# LEDpanel7-20.net
KiCad netlist of a schematic drawn in EAGLE
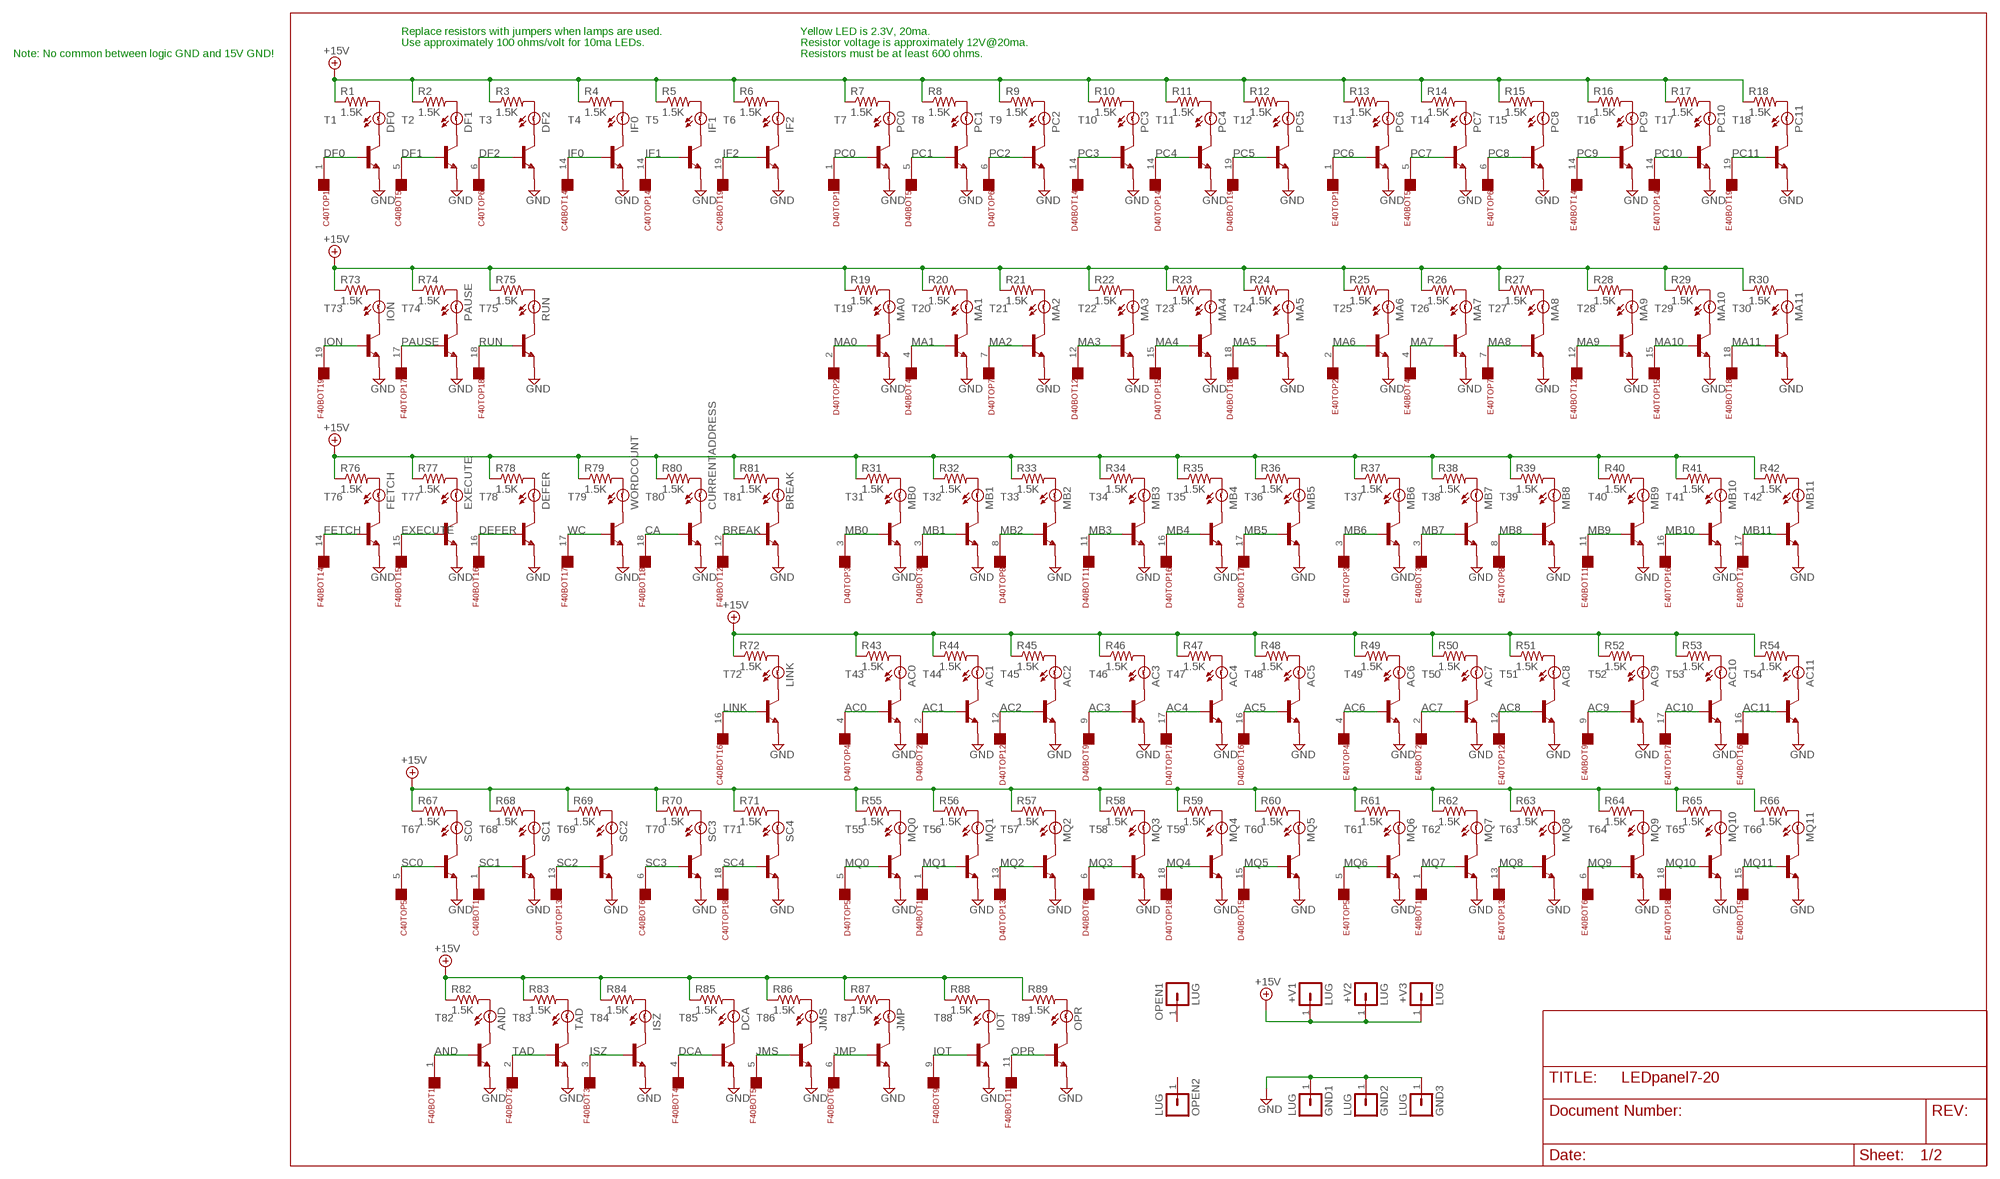
[diagram p0: schematic, sheet 1]
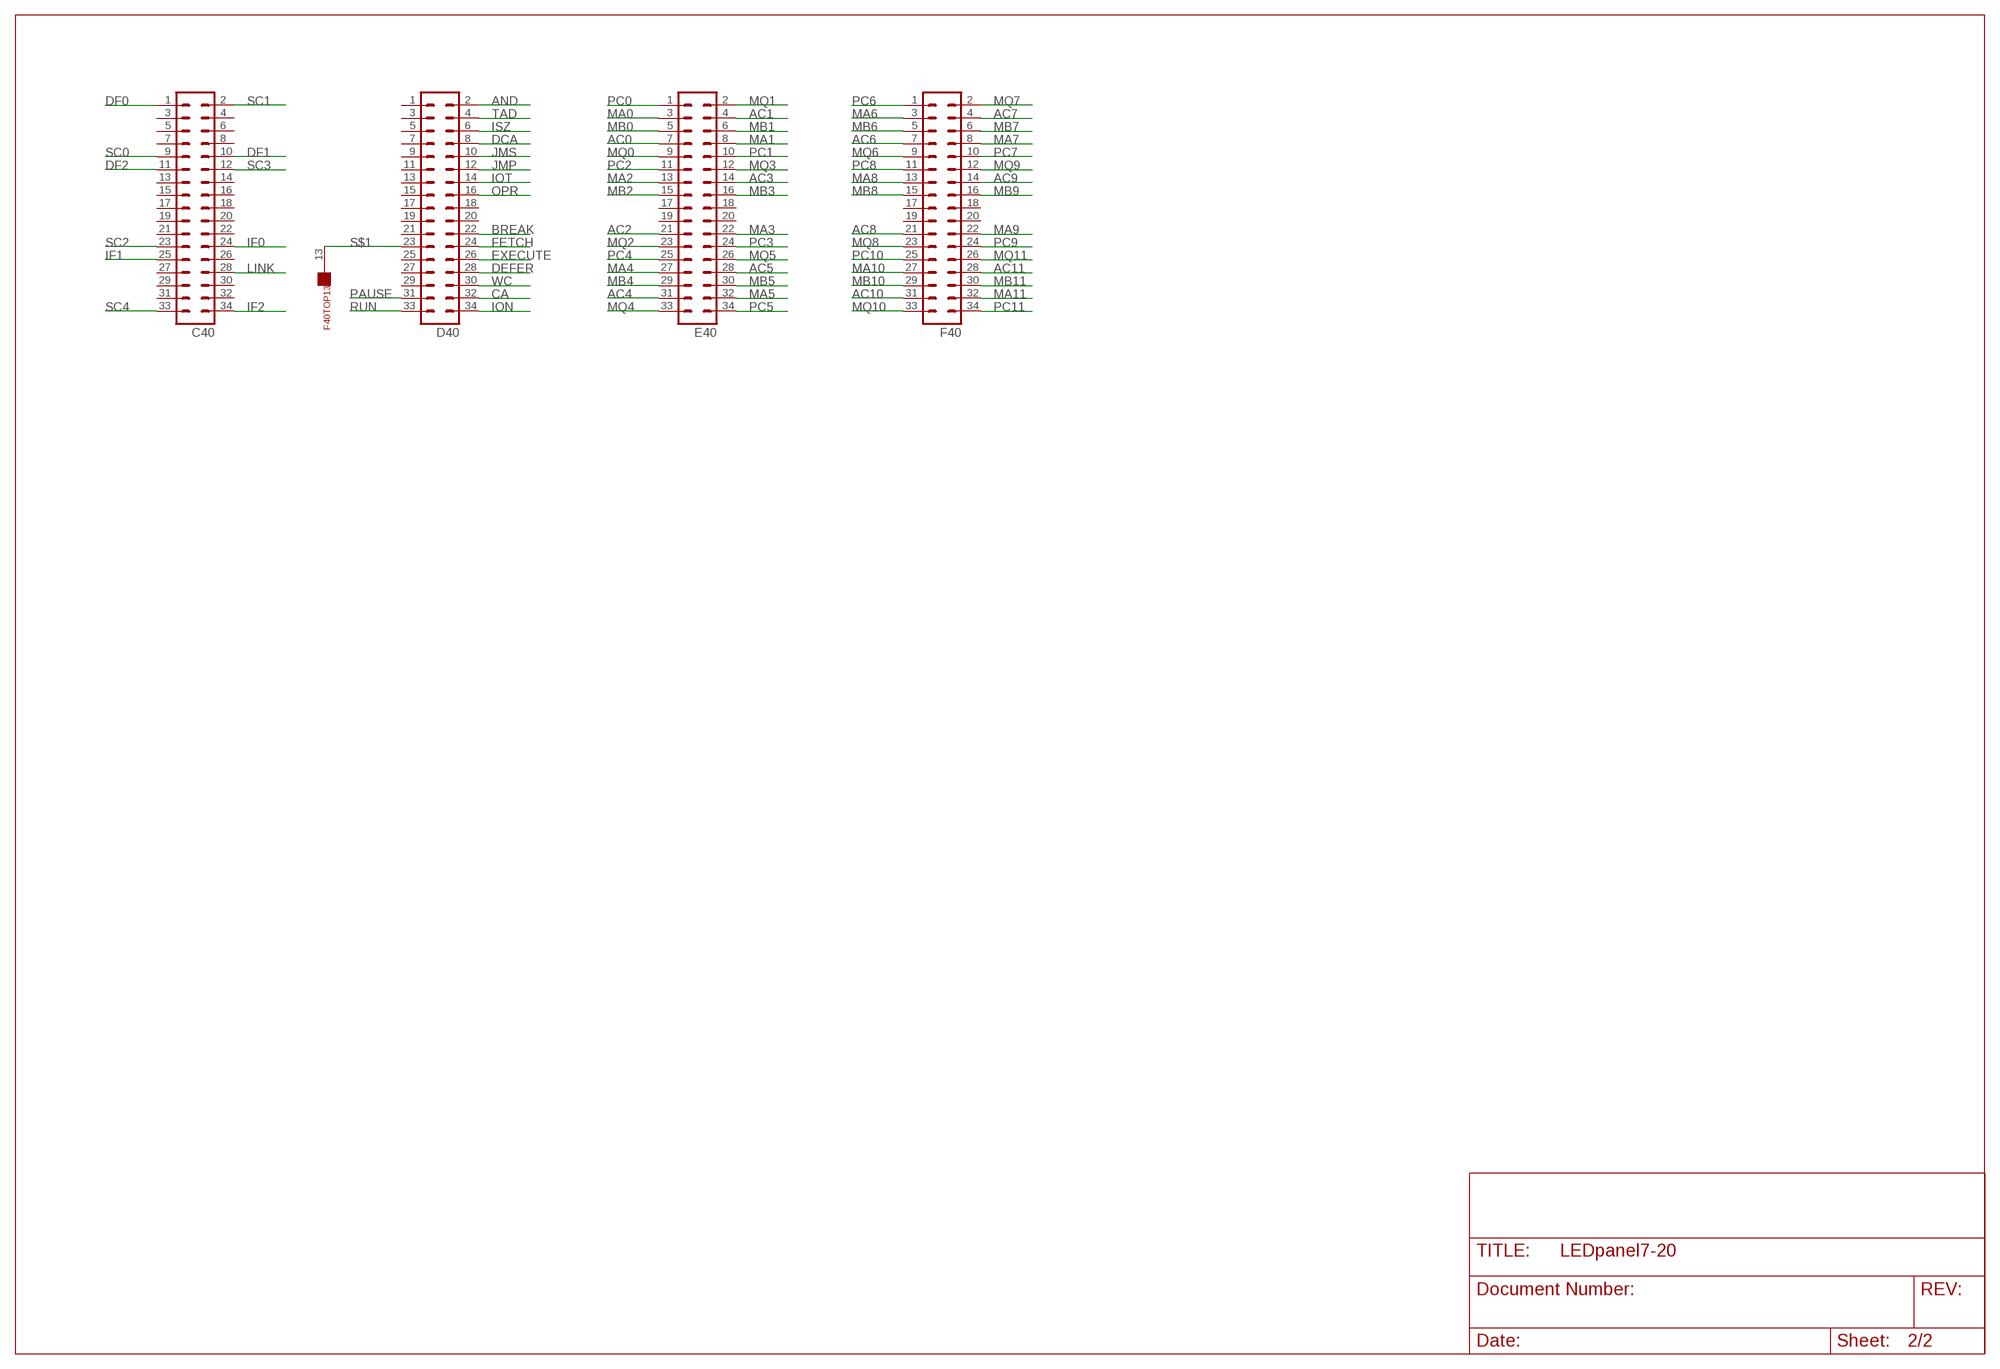
[diagram p1: schematic, sheet 2]

(export (version "E")
  (design (tool "Eeschema 10.0.6"))
  (components
    (comp (ref "C40")
      (value "ML34")
      (footprint "eagle-import:ML34")
      (libsource (lib "eagle-import") (part "ML34"))
    )
    (comp (ref "D40")
      (value "ML34")
      (footprint "eagle-import:ML34")
      (libsource (lib "eagle-import") (part "ML34"))
    )
    (comp (ref "E40")
      (value "ML34")
      (footprint "eagle-import:ML34")
      (libsource (lib "eagle-import") (part "ML34"))
    )
    (comp (ref "F40")
      (value "ML34")
      (footprint "eagle-import:ML34")
      (libsource (lib "eagle-import") (part "ML34"))
    )
    (comp (ref "F40TOP")
      (value "FLEX19")
      (footprint "eagle-import:FLEX19")
      (libsource (lib "eagle-import") (part "FLEX19"))
    )
    (comp (ref "+V1")
      (value "LUG")
      (footprint "eagle-import:SPADELUG")
      (libsource (lib "eagle-import") (part "LUG"))
    )
    (comp (ref "+V2")
      (value "LUG")
      (footprint "eagle-import:SPADELUG")
      (libsource (lib "eagle-import") (part "LUG"))
    )
    (comp (ref "+V3")
      (value "LUG")
      (footprint "eagle-import:SPADELUG")
      (libsource (lib "eagle-import") (part "LUG"))
    )
    (comp (ref "AC0")
      (value "BULB")
      (footprint "eagle-import:BULB")
      (libsource (lib "eagle-import") (part "BULB"))
    )
    (comp (ref "AC1")
      (value "BULB")
      (footprint "eagle-import:BULB")
      (libsource (lib "eagle-import") (part "BULB"))
    )
    (comp (ref "AC2")
      (value "BULB")
      (footprint "eagle-import:BULB")
      (libsource (lib "eagle-import") (part "BULB"))
    )
    (comp (ref "AC3")
      (value "BULB")
      (footprint "eagle-import:BULB")
      (libsource (lib "eagle-import") (part "BULB"))
    )
    (comp (ref "AC4")
      (value "BULB")
      (footprint "eagle-import:BULB")
      (libsource (lib "eagle-import") (part "BULB"))
    )
    (comp (ref "AC5")
      (value "BULB")
      (footprint "eagle-import:BULB")
      (libsource (lib "eagle-import") (part "BULB"))
    )
    (comp (ref "AC6")
      (value "BULB")
      (footprint "eagle-import:BULB")
      (libsource (lib "eagle-import") (part "BULB"))
    )
    (comp (ref "AC7")
      (value "BULB")
      (footprint "eagle-import:BULB")
      (libsource (lib "eagle-import") (part "BULB"))
    )
    (comp (ref "AC8")
      (value "BULB")
      (footprint "eagle-import:BULB")
      (libsource (lib "eagle-import") (part "BULB"))
    )
    (comp (ref "AC9")
      (value "BULB")
      (footprint "eagle-import:BULB")
      (libsource (lib "eagle-import") (part "BULB"))
    )
    (comp (ref "AC10")
      (value "BULB")
      (footprint "eagle-import:BULB")
      (libsource (lib "eagle-import") (part "BULB"))
    )
    (comp (ref "AC11")
      (value "BULB")
      (footprint "eagle-import:BULB")
      (libsource (lib "eagle-import") (part "BULB"))
    )
    (comp (ref "AND")
      (value "BULB")
      (footprint "eagle-import:BULB")
      (libsource (lib "eagle-import") (part "BULB"))
    )
    (comp (ref "BREAK")
      (value "BULB")
      (footprint "eagle-import:BULB")
      (libsource (lib "eagle-import") (part "BULB"))
    )
    (comp (ref "C40BOT")
      (value "FLEX19")
      (footprint "eagle-import:FLEX19")
      (libsource (lib "eagle-import") (part "FLEX19"))
    )
    (comp (ref "C40TOP")
      (value "FLEX19")
      (footprint "eagle-import:FLEX19")
      (libsource (lib "eagle-import") (part "FLEX19"))
    )
    (comp (ref "CURRENTADDRESS")
      (value "BULB")
      (footprint "eagle-import:BULB")
      (libsource (lib "eagle-import") (part "BULB"))
    )
    (comp (ref "D40BOT")
      (value "FLEX19")
      (footprint "eagle-import:FLEX19")
      (libsource (lib "eagle-import") (part "FLEX19"))
    )
    (comp (ref "D40TOP")
      (value "FLEX19")
      (footprint "eagle-import:FLEX19")
      (libsource (lib "eagle-import") (part "FLEX19"))
    )
    (comp (ref "DCA")
      (value "BULB")
      (footprint "eagle-import:BULB")
      (libsource (lib "eagle-import") (part "BULB"))
    )
    (comp (ref "DEFER")
      (value "BULB")
      (footprint "eagle-import:BULB")
      (libsource (lib "eagle-import") (part "BULB"))
    )
    (comp (ref "DF0")
      (value "BULB")
      (footprint "eagle-import:BULB")
      (libsource (lib "eagle-import") (part "BULB"))
    )
    (comp (ref "DF1")
      (value "BULB")
      (footprint "eagle-import:BULB")
      (libsource (lib "eagle-import") (part "BULB"))
    )
    (comp (ref "DF2")
      (value "BULB")
      (footprint "eagle-import:BULB")
      (libsource (lib "eagle-import") (part "BULB"))
    )
    (comp (ref "E40BOT")
      (value "FLEX19")
      (footprint "eagle-import:FLEX19")
      (libsource (lib "eagle-import") (part "FLEX19"))
    )
    (comp (ref "E40TOP")
      (value "FLEX19")
      (footprint "eagle-import:FLEX19")
      (libsource (lib "eagle-import") (part "FLEX19"))
    )
    (comp (ref "EXECUTE")
      (value "BULB")
      (footprint "eagle-import:BULB")
      (libsource (lib "eagle-import") (part "BULB"))
    )
    (comp (ref "F40BOT")
      (value "FLEX19")
      (footprint "eagle-import:FLEX19")
      (libsource (lib "eagle-import") (part "FLEX19"))
    )
    (comp (ref "FETCH")
      (value "BULB")
      (footprint "eagle-import:BULB")
      (libsource (lib "eagle-import") (part "BULB"))
    )
    (comp (ref "GND1")
      (value "LUG")
      (footprint "eagle-import:SPADELUG")
      (libsource (lib "eagle-import") (part "LUG"))
    )
    (comp (ref "GND2")
      (value "LUG")
      (footprint "eagle-import:SPADELUG")
      (libsource (lib "eagle-import") (part "LUG"))
    )
    (comp (ref "GND3")
      (value "LUG")
      (footprint "eagle-import:SPADELUG")
      (libsource (lib "eagle-import") (part "LUG"))
    )
    (comp (ref "IF0")
      (value "BULB")
      (footprint "eagle-import:BULB")
      (libsource (lib "eagle-import") (part "BULB"))
    )
    (comp (ref "IF1")
      (value "BULB")
      (footprint "eagle-import:BULB")
      (libsource (lib "eagle-import") (part "BULB"))
    )
    (comp (ref "IF2")
      (value "BULB")
      (footprint "eagle-import:BULB")
      (libsource (lib "eagle-import") (part "BULB"))
    )
    (comp (ref "ION")
      (value "BULB")
      (footprint "eagle-import:BULB")
      (libsource (lib "eagle-import") (part "BULB"))
    )
    (comp (ref "IOT")
      (value "BULB")
      (footprint "eagle-import:BULB")
      (libsource (lib "eagle-import") (part "BULB"))
    )
    (comp (ref "ISZ")
      (value "BULB")
      (footprint "eagle-import:BULB")
      (libsource (lib "eagle-import") (part "BULB"))
    )
    (comp (ref "JMP")
      (value "BULB")
      (footprint "eagle-import:BULB")
      (libsource (lib "eagle-import") (part "BULB"))
    )
    (comp (ref "JMS")
      (value "BULB")
      (footprint "eagle-import:BULB")
      (libsource (lib "eagle-import") (part "BULB"))
    )
    (comp (ref "LINK")
      (value "BULB")
      (footprint "eagle-import:BULB")
      (libsource (lib "eagle-import") (part "BULB"))
    )
    (comp (ref "MA0")
      (value "BULB")
      (footprint "eagle-import:BULB")
      (libsource (lib "eagle-import") (part "BULB"))
    )
    (comp (ref "MA1")
      (value "BULB")
      (footprint "eagle-import:BULB")
      (libsource (lib "eagle-import") (part "BULB"))
    )
    (comp (ref "MA2")
      (value "BULB")
      (footprint "eagle-import:BULB")
      (libsource (lib "eagle-import") (part "BULB"))
    )
    (comp (ref "MA3")
      (value "BULB")
      (footprint "eagle-import:BULB")
      (libsource (lib "eagle-import") (part "BULB"))
    )
    (comp (ref "MA4")
      (value "BULB")
      (footprint "eagle-import:BULB")
      (libsource (lib "eagle-import") (part "BULB"))
    )
    (comp (ref "MA5")
      (value "BULB")
      (footprint "eagle-import:BULB")
      (libsource (lib "eagle-import") (part "BULB"))
    )
    (comp (ref "MA6")
      (value "BULB")
      (footprint "eagle-import:BULB")
      (libsource (lib "eagle-import") (part "BULB"))
    )
    (comp (ref "MA7")
      (value "BULB")
      (footprint "eagle-import:BULB")
      (libsource (lib "eagle-import") (part "BULB"))
    )
    (comp (ref "MA8")
      (value "BULB")
      (footprint "eagle-import:BULB")
      (libsource (lib "eagle-import") (part "BULB"))
    )
    (comp (ref "MA9")
      (value "BULB")
      (footprint "eagle-import:BULB")
      (libsource (lib "eagle-import") (part "BULB"))
    )
    (comp (ref "MA10")
      (value "BULB")
      (footprint "eagle-import:BULB")
      (libsource (lib "eagle-import") (part "BULB"))
    )
    (comp (ref "MA11")
      (value "BULB")
      (footprint "eagle-import:BULB")
      (libsource (lib "eagle-import") (part "BULB"))
    )
    (comp (ref "MB0")
      (value "BULB")
      (footprint "eagle-import:BULB")
      (libsource (lib "eagle-import") (part "BULB"))
    )
    (comp (ref "MB1")
      (value "BULB")
      (footprint "eagle-import:BULB")
      (libsource (lib "eagle-import") (part "BULB"))
    )
    (comp (ref "MB2")
      (value "BULB")
      (footprint "eagle-import:BULB")
      (libsource (lib "eagle-import") (part "BULB"))
    )
    (comp (ref "MB3")
      (value "BULB")
      (footprint "eagle-import:BULB")
      (libsource (lib "eagle-import") (part "BULB"))
    )
    (comp (ref "MB4")
      (value "BULB")
      (footprint "eagle-import:BULB")
      (libsource (lib "eagle-import") (part "BULB"))
    )
    (comp (ref "MB5")
      (value "BULB")
      (footprint "eagle-import:BULB")
      (libsource (lib "eagle-import") (part "BULB"))
    )
    (comp (ref "MB6")
      (value "BULB")
      (footprint "eagle-import:BULB")
      (libsource (lib "eagle-import") (part "BULB"))
    )
    (comp (ref "MB7")
      (value "BULB")
      (footprint "eagle-import:BULB")
      (libsource (lib "eagle-import") (part "BULB"))
    )
    (comp (ref "MB8")
      (value "BULB")
      (footprint "eagle-import:BULB")
      (libsource (lib "eagle-import") (part "BULB"))
    )
    (comp (ref "MB9")
      (value "BULB")
      (footprint "eagle-import:BULB")
      (libsource (lib "eagle-import") (part "BULB"))
    )
    (comp (ref "MB10")
      (value "BULB")
      (footprint "eagle-import:BULB")
      (libsource (lib "eagle-import") (part "BULB"))
    )
    (comp (ref "MB11")
      (value "BULB")
      (footprint "eagle-import:BULB")
      (libsource (lib "eagle-import") (part "BULB"))
    )
    (comp (ref "MQ0")
      (value "BULB")
      (footprint "eagle-import:BULB")
      (libsource (lib "eagle-import") (part "BULB"))
    )
    (comp (ref "MQ1")
      (value "BULB")
      (footprint "eagle-import:BULB")
      (libsource (lib "eagle-import") (part "BULB"))
    )
    (comp (ref "MQ2")
      (value "BULB")
      (footprint "eagle-import:BULB")
      (libsource (lib "eagle-import") (part "BULB"))
    )
    (comp (ref "MQ3")
      (value "BULB")
      (footprint "eagle-import:BULB")
      (libsource (lib "eagle-import") (part "BULB"))
    )
    (comp (ref "MQ4")
      (value "BULB")
      (footprint "eagle-import:BULB")
      (libsource (lib "eagle-import") (part "BULB"))
    )
    (comp (ref "MQ5")
      (value "BULB")
      (footprint "eagle-import:BULB")
      (libsource (lib "eagle-import") (part "BULB"))
    )
    (comp (ref "MQ6")
      (value "BULB")
      (footprint "eagle-import:BULB")
      (libsource (lib "eagle-import") (part "BULB"))
    )
    (comp (ref "MQ7")
      (value "BULB")
      (footprint "eagle-import:BULB")
      (libsource (lib "eagle-import") (part "BULB"))
    )
    (comp (ref "MQ8")
      (value "BULB")
      (footprint "eagle-import:BULB")
      (libsource (lib "eagle-import") (part "BULB"))
    )
    (comp (ref "MQ9")
      (value "BULB")
      (footprint "eagle-import:BULB")
      (libsource (lib "eagle-import") (part "BULB"))
    )
    (comp (ref "MQ10")
      (value "BULB")
      (footprint "eagle-import:BULB")
      (libsource (lib "eagle-import") (part "BULB"))
    )
    (comp (ref "MQ11")
      (value "BULB")
      (footprint "eagle-import:BULB")
      (libsource (lib "eagle-import") (part "BULB"))
    )
    (comp (ref "OPEN1")
      (value "LUG")
      (footprint "eagle-import:SPADELUG")
      (libsource (lib "eagle-import") (part "LUG"))
    )
    (comp (ref "OPEN2")
      (value "LUG")
      (footprint "eagle-import:SPADELUG")
      (libsource (lib "eagle-import") (part "LUG"))
    )
    (comp (ref "OPR")
      (value "BULB")
      (footprint "eagle-import:BULB")
      (libsource (lib "eagle-import") (part "BULB"))
    )
    (comp (ref "PAUSE")
      (value "BULB")
      (footprint "eagle-import:BULB")
      (libsource (lib "eagle-import") (part "BULB"))
    )
    (comp (ref "PC0")
      (value "BULB")
      (footprint "eagle-import:BULB")
      (libsource (lib "eagle-import") (part "BULB"))
    )
    (comp (ref "PC1")
      (value "BULB")
      (footprint "eagle-import:BULB")
      (libsource (lib "eagle-import") (part "BULB"))
    )
    (comp (ref "PC2")
      (value "BULB")
      (footprint "eagle-import:BULB")
      (libsource (lib "eagle-import") (part "BULB"))
    )
    (comp (ref "PC3")
      (value "BULB")
      (footprint "eagle-import:BULB")
      (libsource (lib "eagle-import") (part "BULB"))
    )
    (comp (ref "PC4")
      (value "BULB")
      (footprint "eagle-import:BULB")
      (libsource (lib "eagle-import") (part "BULB"))
    )
    (comp (ref "PC5")
      (value "BULB")
      (footprint "eagle-import:BULB")
      (libsource (lib "eagle-import") (part "BULB"))
    )
    (comp (ref "PC6")
      (value "BULB")
      (footprint "eagle-import:BULB")
      (libsource (lib "eagle-import") (part "BULB"))
    )
    (comp (ref "PC7")
      (value "BULB")
      (footprint "eagle-import:BULB")
      (libsource (lib "eagle-import") (part "BULB"))
    )
    (comp (ref "PC8")
      (value "BULB")
      (footprint "eagle-import:BULB")
      (libsource (lib "eagle-import") (part "BULB"))
    )
    (comp (ref "PC9")
      (value "BULB")
      (footprint "eagle-import:BULB")
      (libsource (lib "eagle-import") (part "BULB"))
    )
    (comp (ref "PC10")
      (value "BULB")
      (footprint "eagle-import:BULB")
      (libsource (lib "eagle-import") (part "BULB"))
    )
    (comp (ref "PC11")
      (value "BULB")
      (footprint "eagle-import:BULB")
      (libsource (lib "eagle-import") (part "BULB"))
    )
    (comp (ref "R1")
      (value "1.5K")
      (footprint "eagle-import:0207_10")
      (libsource (lib "eagle-import") (part "R-US_0207/10"))
    )
    (comp (ref "R2")
      (value "1.5K")
      (footprint "eagle-import:0207_10")
      (libsource (lib "eagle-import") (part "R-US_0207/10"))
    )
    (comp (ref "R3")
      (value "1.5K")
      (footprint "eagle-import:0207_10")
      (libsource (lib "eagle-import") (part "R-US_0207/10"))
    )
    (comp (ref "R4")
      (value "1.5K")
      (footprint "eagle-import:0207_10")
      (libsource (lib "eagle-import") (part "R-US_0207/10"))
    )
    (comp (ref "R5")
      (value "1.5K")
      (footprint "eagle-import:0207_10")
      (libsource (lib "eagle-import") (part "R-US_0207/10"))
    )
    (comp (ref "R6")
      (value "1.5K")
      (footprint "eagle-import:0207_10")
      (libsource (lib "eagle-import") (part "R-US_0207/10"))
    )
    (comp (ref "R7")
      (value "1.5K")
      (footprint "eagle-import:0207_10")
      (libsource (lib "eagle-import") (part "R-US_0207/10"))
    )
    (comp (ref "R8")
      (value "1.5K")
      (footprint "eagle-import:0207_10")
      (libsource (lib "eagle-import") (part "R-US_0207/10"))
    )
    (comp (ref "R9")
      (value "1.5K")
      (footprint "eagle-import:0207_10")
      (libsource (lib "eagle-import") (part "R-US_0207/10"))
    )
    (comp (ref "R10")
      (value "1.5K")
      (footprint "eagle-import:0207_10")
      (libsource (lib "eagle-import") (part "R-US_0207/10"))
    )
    (comp (ref "R11")
      (value "1.5K")
      (footprint "eagle-import:0207_10")
      (libsource (lib "eagle-import") (part "R-US_0207/10"))
    )
    (comp (ref "R12")
      (value "1.5K")
      (footprint "eagle-import:0207_10")
      (libsource (lib "eagle-import") (part "R-US_0207/10"))
    )
    (comp (ref "R13")
      (value "1.5K")
      (footprint "eagle-import:0207_10")
      (libsource (lib "eagle-import") (part "R-US_0207/10"))
    )
    (comp (ref "R14")
      (value "1.5K")
      (footprint "eagle-import:0207_10")
      (libsource (lib "eagle-import") (part "R-US_0207/10"))
    )
    (comp (ref "R15")
      (value "1.5K")
      (footprint "eagle-import:0207_10")
      (libsource (lib "eagle-import") (part "R-US_0207/10"))
    )
    (comp (ref "R16")
      (value "1.5K")
      (footprint "eagle-import:0207_10")
      (libsource (lib "eagle-import") (part "R-US_0207/10"))
    )
    (comp (ref "R17")
      (value "1.5K")
      (footprint "eagle-import:0207_10")
      (libsource (lib "eagle-import") (part "R-US_0207/10"))
    )
    (comp (ref "R18")
      (value "1.5K")
      (footprint "eagle-import:0207_10")
      (libsource (lib "eagle-import") (part "R-US_0207/10"))
    )
    (comp (ref "R19")
      (value "1.5K")
      (footprint "eagle-import:0207_10")
      (libsource (lib "eagle-import") (part "R-US_0207/10"))
    )
    (comp (ref "R20")
      (value "1.5K")
      (footprint "eagle-import:0207_10")
      (libsource (lib "eagle-import") (part "R-US_0207/10"))
    )
    (comp (ref "R21")
      (value "1.5K")
      (footprint "eagle-import:0207_10")
      (libsource (lib "eagle-import") (part "R-US_0207/10"))
    )
    (comp (ref "R22")
      (value "1.5K")
      (footprint "eagle-import:0207_10")
      (libsource (lib "eagle-import") (part "R-US_0207/10"))
    )
    (comp (ref "R23")
      (value "1.5K")
      (footprint "eagle-import:0207_10")
      (libsource (lib "eagle-import") (part "R-US_0207/10"))
    )
    (comp (ref "R24")
      (value "1.5K")
      (footprint "eagle-import:0207_10")
      (libsource (lib "eagle-import") (part "R-US_0207/10"))
    )
    (comp (ref "R25")
      (value "1.5K")
      (footprint "eagle-import:0207_10")
      (libsource (lib "eagle-import") (part "R-US_0207/10"))
    )
    (comp (ref "R26")
      (value "1.5K")
      (footprint "eagle-import:0207_10")
      (libsource (lib "eagle-import") (part "R-US_0207/10"))
    )
    (comp (ref "R27")
      (value "1.5K")
      (footprint "eagle-import:0207_10")
      (libsource (lib "eagle-import") (part "R-US_0207/10"))
    )
    (comp (ref "R28")
      (value "1.5K")
      (footprint "eagle-import:0207_10")
      (libsource (lib "eagle-import") (part "R-US_0207/10"))
    )
    (comp (ref "R29")
      (value "1.5K")
      (footprint "eagle-import:0207_10")
      (libsource (lib "eagle-import") (part "R-US_0207/10"))
    )
    (comp (ref "R30")
      (value "1.5K")
      (footprint "eagle-import:0207_10")
      (libsource (lib "eagle-import") (part "R-US_0207/10"))
    )
    (comp (ref "R31")
      (value "1.5K")
      (footprint "eagle-import:0207_10")
      (libsource (lib "eagle-import") (part "R-US_0207/10"))
    )
    (comp (ref "R32")
      (value "1.5K")
      (footprint "eagle-import:0207_10")
      (libsource (lib "eagle-import") (part "R-US_0207/10"))
    )
    (comp (ref "R33")
      (value "1.5K")
      (footprint "eagle-import:0207_10")
      (libsource (lib "eagle-import") (part "R-US_0207/10"))
    )
    (comp (ref "R34")
      (value "1.5K")
      (footprint "eagle-import:0207_10")
      (libsource (lib "eagle-import") (part "R-US_0207/10"))
    )
    (comp (ref "R35")
      (value "1.5K")
      (footprint "eagle-import:0207_10")
      (libsource (lib "eagle-import") (part "R-US_0207/10"))
    )
    (comp (ref "R36")
      (value "1.5K")
      (footprint "eagle-import:0207_10")
      (libsource (lib "eagle-import") (part "R-US_0207/10"))
    )
    (comp (ref "R37")
      (value "1.5K")
      (footprint "eagle-import:0207_10")
      (libsource (lib "eagle-import") (part "R-US_0207/10"))
    )
    (comp (ref "R38")
      (value "1.5K")
      (footprint "eagle-import:0207_10")
      (libsource (lib "eagle-import") (part "R-US_0207/10"))
    )
    (comp (ref "R39")
      (value "1.5K")
      (footprint "eagle-import:0207_10")
      (libsource (lib "eagle-import") (part "R-US_0207/10"))
    )
    (comp (ref "R40")
      (value "1.5K")
      (footprint "eagle-import:0207_10")
      (libsource (lib "eagle-import") (part "R-US_0207/10"))
    )
    (comp (ref "R41")
      (value "1.5K")
      (footprint "eagle-import:0207_10")
      (libsource (lib "eagle-import") (part "R-US_0207/10"))
    )
    (comp (ref "R42")
      (value "1.5K")
      (footprint "eagle-import:0207_10")
      (libsource (lib "eagle-import") (part "R-US_0207/10"))
    )
    (comp (ref "R43")
      (value "1.5K")
      (footprint "eagle-import:0207_10")
      (libsource (lib "eagle-import") (part "R-US_0207/10"))
    )
    (comp (ref "R44")
      (value "1.5K")
      (footprint "eagle-import:0207_10")
      (libsource (lib "eagle-import") (part "R-US_0207/10"))
    )
    (comp (ref "R45")
      (value "1.5K")
      (footprint "eagle-import:0207_10")
      (libsource (lib "eagle-import") (part "R-US_0207/10"))
    )
    (comp (ref "R46")
      (value "1.5K")
      (footprint "eagle-import:0207_10")
      (libsource (lib "eagle-import") (part "R-US_0207/10"))
    )
    (comp (ref "R47")
      (value "1.5K")
      (footprint "eagle-import:0207_10")
      (libsource (lib "eagle-import") (part "R-US_0207/10"))
    )
    (comp (ref "R48")
      (value "1.5K")
      (footprint "eagle-import:0207_10")
      (libsource (lib "eagle-import") (part "R-US_0207/10"))
    )
    (comp (ref "R49")
      (value "1.5K")
      (footprint "eagle-import:0207_10")
      (libsource (lib "eagle-import") (part "R-US_0207/10"))
    )
    (comp (ref "R50")
      (value "1.5K")
      (footprint "eagle-import:0207_10")
      (libsource (lib "eagle-import") (part "R-US_0207/10"))
    )
    (comp (ref "R51")
      (value "1.5K")
      (footprint "eagle-import:0207_10")
      (libsource (lib "eagle-import") (part "R-US_0207/10"))
    )
    (comp (ref "R52")
      (value "1.5K")
      (footprint "eagle-import:0207_10")
      (libsource (lib "eagle-import") (part "R-US_0207/10"))
    )
    (comp (ref "R53")
      (value "1.5K")
      (footprint "eagle-import:0207_10")
      (libsource (lib "eagle-import") (part "R-US_0207/10"))
    )
    (comp (ref "R54")
      (value "1.5K")
      (footprint "eagle-import:0207_10")
      (libsource (lib "eagle-import") (part "R-US_0207/10"))
    )
    (comp (ref "R55")
      (value "1.5K")
      (footprint "eagle-import:0207_10")
      (libsource (lib "eagle-import") (part "R-US_0207/10"))
    )
    (comp (ref "R56")
      (value "1.5K")
      (footprint "eagle-import:0207_10")
      (libsource (lib "eagle-import") (part "R-US_0207/10"))
    )
    (comp (ref "R57")
      (value "1.5K")
      (footprint "eagle-import:0207_10")
      (libsource (lib "eagle-import") (part "R-US_0207/10"))
    )
    (comp (ref "R58")
      (value "1.5K")
      (footprint "eagle-import:0207_10")
      (libsource (lib "eagle-import") (part "R-US_0207/10"))
    )
    (comp (ref "R59")
      (value "1.5K")
      (footprint "eagle-import:0207_10")
      (libsource (lib "eagle-import") (part "R-US_0207/10"))
    )
    (comp (ref "R60")
      (value "1.5K")
      (footprint "eagle-import:0207_10")
      (libsource (lib "eagle-import") (part "R-US_0207/10"))
    )
    (comp (ref "R61")
      (value "1.5K")
      (footprint "eagle-import:0207_10")
      (libsource (lib "eagle-import") (part "R-US_0207/10"))
    )
    (comp (ref "R62")
      (value "1.5K")
      (footprint "eagle-import:0207_10")
      (libsource (lib "eagle-import") (part "R-US_0207/10"))
    )
    (comp (ref "R63")
      (value "1.5K")
      (footprint "eagle-import:0207_10")
      (libsource (lib "eagle-import") (part "R-US_0207/10"))
    )
    (comp (ref "R64")
      (value "1.5K")
      (footprint "eagle-import:0207_10")
      (libsource (lib "eagle-import") (part "R-US_0207/10"))
    )
    (comp (ref "R65")
      (value "1.5K")
      (footprint "eagle-import:0207_10")
      (libsource (lib "eagle-import") (part "R-US_0207/10"))
    )
    (comp (ref "R66")
      (value "1.5K")
      (footprint "eagle-import:0207_10")
      (libsource (lib "eagle-import") (part "R-US_0207/10"))
    )
    (comp (ref "R67")
      (value "1.5K")
      (footprint "eagle-import:0207_10")
      (libsource (lib "eagle-import") (part "R-US_0207/10"))
    )
    (comp (ref "R68")
      (value "1.5K")
      (footprint "eagle-import:0207_10")
      (libsource (lib "eagle-import") (part "R-US_0207/10"))
    )
    (comp (ref "R69")
      (value "1.5K")
      (footprint "eagle-import:0207_10")
      (libsource (lib "eagle-import") (part "R-US_0207/10"))
    )
    (comp (ref "R70")
      (value "1.5K")
      (footprint "eagle-import:0207_10")
      (libsource (lib "eagle-import") (part "R-US_0207/10"))
    )
    (comp (ref "R71")
      (value "1.5K")
      (footprint "eagle-import:0207_10")
      (libsource (lib "eagle-import") (part "R-US_0207/10"))
    )
    (comp (ref "R72")
      (value "1.5K")
      (footprint "eagle-import:0207_10")
      (libsource (lib "eagle-import") (part "R-US_0207/10"))
    )
    (comp (ref "R73")
      (value "1.5K")
      (footprint "eagle-import:0207_10")
      (libsource (lib "eagle-import") (part "R-US_0207/10"))
    )
    (comp (ref "R74")
      (value "1.5K")
      (footprint "eagle-import:0207_10")
      (libsource (lib "eagle-import") (part "R-US_0207/10"))
    )
    (comp (ref "R75")
      (value "1.5K")
      (footprint "eagle-import:0207_10")
      (libsource (lib "eagle-import") (part "R-US_0207/10"))
    )
    (comp (ref "R76")
      (value "1.5K")
      (footprint "eagle-import:0207_10")
      (libsource (lib "eagle-import") (part "R-US_0207/10"))
    )
    (comp (ref "R77")
      (value "1.5K")
      (footprint "eagle-import:0207_10")
      (libsource (lib "eagle-import") (part "R-US_0207/10"))
    )
    (comp (ref "R78")
      (value "1.5K")
      (footprint "eagle-import:0207_10")
      (libsource (lib "eagle-import") (part "R-US_0207/10"))
    )
    (comp (ref "R79")
      (value "1.5K")
      (footprint "eagle-import:0207_10")
      (libsource (lib "eagle-import") (part "R-US_0207/10"))
    )
    (comp (ref "R80")
      (value "1.5K")
      (footprint "eagle-import:0207_10")
      (libsource (lib "eagle-import") (part "R-US_0207/10"))
    )
    (comp (ref "R81")
      (value "1.5K")
      (footprint "eagle-import:0207_10")
      (libsource (lib "eagle-import") (part "R-US_0207/10"))
    )
    (comp (ref "R82")
      (value "1.5K")
      (footprint "eagle-import:0207_10")
      (libsource (lib "eagle-import") (part "R-US_0207/10"))
    )
    (comp (ref "R83")
      (value "1.5K")
      (footprint "eagle-import:0207_10")
      (libsource (lib "eagle-import") (part "R-US_0207/10"))
    )
    (comp (ref "R84")
      (value "1.5K")
      (footprint "eagle-import:0207_10")
      (libsource (lib "eagle-import") (part "R-US_0207/10"))
    )
    (comp (ref "R85")
      (value "1.5K")
      (footprint "eagle-import:0207_10")
      (libsource (lib "eagle-import") (part "R-US_0207/10"))
    )
    (comp (ref "R86")
      (value "1.5K")
      (footprint "eagle-import:0207_10")
      (libsource (lib "eagle-import") (part "R-US_0207/10"))
    )
    (comp (ref "R87")
      (value "1.5K")
      (footprint "eagle-import:0207_10")
      (libsource (lib "eagle-import") (part "R-US_0207/10"))
    )
    (comp (ref "R88")
      (value "1.5K")
      (footprint "eagle-import:0207_10")
      (libsource (lib "eagle-import") (part "R-US_0207/10"))
    )
    (comp (ref "R89")
      (value "1.5K")
      (footprint "eagle-import:0207_10")
      (libsource (lib "eagle-import") (part "R-US_0207/10"))
    )
    (comp (ref "RUN")
      (value "BULB")
      (footprint "eagle-import:BULB")
      (libsource (lib "eagle-import") (part "BULB"))
    )
    (comp (ref "SC0")
      (value "BULB")
      (footprint "eagle-import:BULB")
      (libsource (lib "eagle-import") (part "BULB"))
    )
    (comp (ref "SC1")
      (value "BULB")
      (footprint "eagle-import:BULB")
      (libsource (lib "eagle-import") (part "BULB"))
    )
    (comp (ref "SC2")
      (value "BULB")
      (footprint "eagle-import:BULB")
      (libsource (lib "eagle-import") (part "BULB"))
    )
    (comp (ref "SC3")
      (value "BULB")
      (footprint "eagle-import:BULB")
      (libsource (lib "eagle-import") (part "BULB"))
    )
    (comp (ref "SC4")
      (value "BULB")
      (footprint "eagle-import:BULB")
      (libsource (lib "eagle-import") (part "BULB"))
    )
    (comp (ref "T1")
      (value "MPS2222A-NPN-TO92-CBE")
      (footprint "eagle-import:TO92-CBE")
      (libsource (lib "eagle-import") (part "-NPN-TO92-CBEMPS2222A"))
    )
    (comp (ref "T2")
      (value "MPS2222A-NPN-TO92-CBE")
      (footprint "eagle-import:TO92-CBE")
      (libsource (lib "eagle-import") (part "-NPN-TO92-CBEMPS2222A"))
    )
    (comp (ref "T3")
      (value "MPS2222A-NPN-TO92-CBE")
      (footprint "eagle-import:TO92-CBE")
      (libsource (lib "eagle-import") (part "-NPN-TO92-CBEMPS2222A"))
    )
    (comp (ref "T4")
      (value "MPS2222A-NPN-TO92-CBE")
      (footprint "eagle-import:TO92-CBE")
      (libsource (lib "eagle-import") (part "-NPN-TO92-CBEMPS2222A"))
    )
    (comp (ref "T5")
      (value "MPS2222A-NPN-TO92-CBE")
      (footprint "eagle-import:TO92-CBE")
      (libsource (lib "eagle-import") (part "-NPN-TO92-CBEMPS2222A"))
    )
    (comp (ref "T6")
      (value "MPS2222A-NPN-TO92-CBE")
      (footprint "eagle-import:TO92-CBE")
      (libsource (lib "eagle-import") (part "-NPN-TO92-CBEMPS2222A"))
    )
    (comp (ref "T7")
      (value "MPS2222A-NPN-TO92-CBE")
      (footprint "eagle-import:TO92-CBE")
      (libsource (lib "eagle-import") (part "-NPN-TO92-CBEMPS2222A"))
    )
    (comp (ref "T8")
      (value "MPS2222A-NPN-TO92-CBE")
      (footprint "eagle-import:TO92-CBE")
      (libsource (lib "eagle-import") (part "-NPN-TO92-CBEMPS2222A"))
    )
    (comp (ref "T9")
      (value "MPS2222A-NPN-TO92-CBE")
      (footprint "eagle-import:TO92-CBE")
      (libsource (lib "eagle-import") (part "-NPN-TO92-CBEMPS2222A"))
    )
    (comp (ref "T10")
      (value "MPS2222A-NPN-TO92-CBE")
      (footprint "eagle-import:TO92-CBE")
      (libsource (lib "eagle-import") (part "-NPN-TO92-CBEMPS2222A"))
    )
    (comp (ref "T11")
      (value "MPS2222A-NPN-TO92-CBE")
      (footprint "eagle-import:TO92-CBE")
      (libsource (lib "eagle-import") (part "-NPN-TO92-CBEMPS2222A"))
    )
    (comp (ref "T12")
      (value "MPS2222A-NPN-TO92-CBE")
      (footprint "eagle-import:TO92-CBE")
      (libsource (lib "eagle-import") (part "-NPN-TO92-CBEMPS2222A"))
    )
    (comp (ref "T13")
      (value "MPS2222A-NPN-TO92-CBE")
      (footprint "eagle-import:TO92-CBE")
      (libsource (lib "eagle-import") (part "-NPN-TO92-CBEMPS2222A"))
    )
    (comp (ref "T14")
      (value "MPS2222A-NPN-TO92-CBE")
      (footprint "eagle-import:TO92-CBE")
      (libsource (lib "eagle-import") (part "-NPN-TO92-CBEMPS2222A"))
    )
    (comp (ref "T15")
      (value "MPS2222A-NPN-TO92-CBE")
      (footprint "eagle-import:TO92-CBE")
      (libsource (lib "eagle-import") (part "-NPN-TO92-CBEMPS2222A"))
    )
    (comp (ref "T16")
      (value "MPS2222A-NPN-TO92-CBE")
      (footprint "eagle-import:TO92-CBE")
      (libsource (lib "eagle-import") (part "-NPN-TO92-CBEMPS2222A"))
    )
    (comp (ref "T17")
      (value "MPS2222A-NPN-TO92-CBE")
      (footprint "eagle-import:TO92-CBE")
      (libsource (lib "eagle-import") (part "-NPN-TO92-CBEMPS2222A"))
    )
    (comp (ref "T18")
      (value "MPS2222A-NPN-TO92-CBE")
      (footprint "eagle-import:TO92-CBE")
      (libsource (lib "eagle-import") (part "-NPN-TO92-CBEMPS2222A"))
    )
    (comp (ref "T19")
      (value "MPS2222A-NPN-TO92-CBE")
      (footprint "eagle-import:TO92-CBE")
      (libsource (lib "eagle-import") (part "-NPN-TO92-CBEMPS2222A"))
    )
    (comp (ref "T20")
      (value "MPS2222A-NPN-TO92-CBE")
      (footprint "eagle-import:TO92-CBE")
      (libsource (lib "eagle-import") (part "-NPN-TO92-CBEMPS2222A"))
    )
    (comp (ref "T21")
      (value "MPS2222A-NPN-TO92-CBE")
      (footprint "eagle-import:TO92-CBE")
      (libsource (lib "eagle-import") (part "-NPN-TO92-CBEMPS2222A"))
    )
    (comp (ref "T22")
      (value "MPS2222A-NPN-TO92-CBE")
      (footprint "eagle-import:TO92-CBE")
      (libsource (lib "eagle-import") (part "-NPN-TO92-CBEMPS2222A"))
    )
    (comp (ref "T23")
      (value "MPS2222A-NPN-TO92-CBE")
      (footprint "eagle-import:TO92-CBE")
      (libsource (lib "eagle-import") (part "-NPN-TO92-CBEMPS2222A"))
    )
    (comp (ref "T24")
      (value "MPS2222A-NPN-TO92-CBE")
      (footprint "eagle-import:TO92-CBE")
      (libsource (lib "eagle-import") (part "-NPN-TO92-CBEMPS2222A"))
    )
    (comp (ref "T25")
      (value "MPS2222A-NPN-TO92-CBE")
      (footprint "eagle-import:TO92-CBE")
      (libsource (lib "eagle-import") (part "-NPN-TO92-CBEMPS2222A"))
    )
    (comp (ref "T26")
      (value "MPS2222A-NPN-TO92-CBE")
      (footprint "eagle-import:TO92-CBE")
      (libsource (lib "eagle-import") (part "-NPN-TO92-CBEMPS2222A"))
    )
    (comp (ref "T27")
      (value "MPS2222A-NPN-TO92-CBE")
      (footprint "eagle-import:TO92-CBE")
      (libsource (lib "eagle-import") (part "-NPN-TO92-CBEMPS2222A"))
    )
    (comp (ref "T28")
      (value "MPS2222A-NPN-TO92-CBE")
      (footprint "eagle-import:TO92-CBE")
      (libsource (lib "eagle-import") (part "-NPN-TO92-CBEMPS2222A"))
    )
    (comp (ref "T29")
      (value "MPS2222A-NPN-TO92-CBE")
      (footprint "eagle-import:TO92-CBE")
      (libsource (lib "eagle-import") (part "-NPN-TO92-CBEMPS2222A"))
    )
    (comp (ref "T30")
      (value "MPS2222A-NPN-TO92-CBE")
      (footprint "eagle-import:TO92-CBE")
      (libsource (lib "eagle-import") (part "-NPN-TO92-CBEMPS2222A"))
    )
    (comp (ref "T31")
      (value "MPS2222A-NPN-TO92-CBE")
      (footprint "eagle-import:TO92-CBE")
      (libsource (lib "eagle-import") (part "-NPN-TO92-CBEMPS2222A"))
    )
    (comp (ref "T32")
      (value "MPS2222A-NPN-TO92-CBE")
      (footprint "eagle-import:TO92-CBE")
      (libsource (lib "eagle-import") (part "-NPN-TO92-CBEMPS2222A"))
    )
    (comp (ref "T33")
      (value "MPS2222A-NPN-TO92-CBE")
      (footprint "eagle-import:TO92-CBE")
      (libsource (lib "eagle-import") (part "-NPN-TO92-CBEMPS2222A"))
    )
    (comp (ref "T34")
      (value "MPS2222A-NPN-TO92-CBE")
      (footprint "eagle-import:TO92-CBE")
      (libsource (lib "eagle-import") (part "-NPN-TO92-CBEMPS2222A"))
    )
    (comp (ref "T35")
      (value "MPS2222A-NPN-TO92-CBE")
      (footprint "eagle-import:TO92-CBE")
      (libsource (lib "eagle-import") (part "-NPN-TO92-CBEMPS2222A"))
    )
    (comp (ref "T36")
      (value "MPS2222A-NPN-TO92-CBE")
      (footprint "eagle-import:TO92-CBE")
      (libsource (lib "eagle-import") (part "-NPN-TO92-CBEMPS2222A"))
    )
    (comp (ref "T37")
      (value "MPS2222A-NPN-TO92-CBE")
      (footprint "eagle-import:TO92-CBE")
      (libsource (lib "eagle-import") (part "-NPN-TO92-CBEMPS2222A"))
    )
    (comp (ref "T38")
      (value "MPS2222A-NPN-TO92-CBE")
      (footprint "eagle-import:TO92-CBE")
      (libsource (lib "eagle-import") (part "-NPN-TO92-CBEMPS2222A"))
    )
    (comp (ref "T39")
      (value "MPS2222A-NPN-TO92-CBE")
      (footprint "eagle-import:TO92-CBE")
      (libsource (lib "eagle-import") (part "-NPN-TO92-CBEMPS2222A"))
    )
    (comp (ref "T40")
      (value "MPS2222A-NPN-TO92-CBE")
      (footprint "eagle-import:TO92-CBE")
      (libsource (lib "eagle-import") (part "-NPN-TO92-CBEMPS2222A"))
    )
    (comp (ref "T41")
      (value "MPS2222A-NPN-TO92-CBE")
      (footprint "eagle-import:TO92-CBE")
      (libsource (lib "eagle-import") (part "-NPN-TO92-CBEMPS2222A"))
    )
    (comp (ref "T42")
      (value "MPS2222A-NPN-TO92-CBE")
      (footprint "eagle-import:TO92-CBE")
      (libsource (lib "eagle-import") (part "-NPN-TO92-CBEMPS2222A"))
    )
    (comp (ref "T43")
      (value "MPS2222A-NPN-TO92-CBE")
      (footprint "eagle-import:TO92-CBE")
      (libsource (lib "eagle-import") (part "-NPN-TO92-CBEMPS2222A"))
    )
    (comp (ref "T44")
      (value "MPS2222A-NPN-TO92-CBE")
      (footprint "eagle-import:TO92-CBE")
      (libsource (lib "eagle-import") (part "-NPN-TO92-CBEMPS2222A"))
    )
    (comp (ref "T45")
      (value "MPS2222A-NPN-TO92-CBE")
      (footprint "eagle-import:TO92-CBE")
      (libsource (lib "eagle-import") (part "-NPN-TO92-CBEMPS2222A"))
    )
    (comp (ref "T46")
      (value "MPS2222A-NPN-TO92-CBE")
      (footprint "eagle-import:TO92-CBE")
      (libsource (lib "eagle-import") (part "-NPN-TO92-CBEMPS2222A"))
    )
    (comp (ref "T47")
      (value "MPS2222A-NPN-TO92-CBE")
      (footprint "eagle-import:TO92-CBE")
      (libsource (lib "eagle-import") (part "-NPN-TO92-CBEMPS2222A"))
    )
    (comp (ref "T48")
      (value "MPS2222A-NPN-TO92-CBE")
      (footprint "eagle-import:TO92-CBE")
      (libsource (lib "eagle-import") (part "-NPN-TO92-CBEMPS2222A"))
    )
    (comp (ref "T49")
      (value "MPS2222A-NPN-TO92-CBE")
      (footprint "eagle-import:TO92-CBE")
      (libsource (lib "eagle-import") (part "-NPN-TO92-CBEMPS2222A"))
    )
    (comp (ref "T50")
      (value "MPS2222A-NPN-TO92-CBE")
      (footprint "eagle-import:TO92-CBE")
      (libsource (lib "eagle-import") (part "-NPN-TO92-CBEMPS2222A"))
    )
    (comp (ref "T51")
      (value "MPS2222A-NPN-TO92-CBE")
      (footprint "eagle-import:TO92-CBE")
      (libsource (lib "eagle-import") (part "-NPN-TO92-CBEMPS2222A"))
    )
    (comp (ref "T52")
      (value "MPS2222A-NPN-TO92-CBE")
      (footprint "eagle-import:TO92-CBE")
      (libsource (lib "eagle-import") (part "-NPN-TO92-CBEMPS2222A"))
    )
    (comp (ref "T53")
      (value "MPS2222A-NPN-TO92-CBE")
      (footprint "eagle-import:TO92-CBE")
      (libsource (lib "eagle-import") (part "-NPN-TO92-CBEMPS2222A"))
    )
    (comp (ref "T54")
      (value "MPS2222A-NPN-TO92-CBE")
      (footprint "eagle-import:TO92-CBE")
      (libsource (lib "eagle-import") (part "-NPN-TO92-CBEMPS2222A"))
    )
    (comp (ref "T55")
      (value "MPS2222A-NPN-TO92-CBE")
      (footprint "eagle-import:TO92-CBE")
      (libsource (lib "eagle-import") (part "-NPN-TO92-CBEMPS2222A"))
    )
    (comp (ref "T56")
      (value "MPS2222A-NPN-TO92-CBE")
      (footprint "eagle-import:TO92-CBE")
      (libsource (lib "eagle-import") (part "-NPN-TO92-CBEMPS2222A"))
    )
    (comp (ref "T57")
      (value "MPS2222A-NPN-TO92-CBE")
      (footprint "eagle-import:TO92-CBE")
      (libsource (lib "eagle-import") (part "-NPN-TO92-CBEMPS2222A"))
    )
    (comp (ref "T58")
      (value "MPS2222A-NPN-TO92-CBE")
      (footprint "eagle-import:TO92-CBE")
      (libsource (lib "eagle-import") (part "-NPN-TO92-CBEMPS2222A"))
    )
    (comp (ref "T59")
      (value "MPS2222A-NPN-TO92-CBE")
      (footprint "eagle-import:TO92-CBE")
      (libsource (lib "eagle-import") (part "-NPN-TO92-CBEMPS2222A"))
    )
    (comp (ref "T60")
      (value "MPS2222A-NPN-TO92-CBE")
      (footprint "eagle-import:TO92-CBE")
      (libsource (lib "eagle-import") (part "-NPN-TO92-CBEMPS2222A"))
    )
    (comp (ref "T61")
      (value "MPS2222A-NPN-TO92-CBE")
      (footprint "eagle-import:TO92-CBE")
      (libsource (lib "eagle-import") (part "-NPN-TO92-CBEMPS2222A"))
    )
    (comp (ref "T62")
      (value "MPS2222A-NPN-TO92-CBE")
      (footprint "eagle-import:TO92-CBE")
      (libsource (lib "eagle-import") (part "-NPN-TO92-CBEMPS2222A"))
    )
    (comp (ref "T63")
      (value "MPS2222A-NPN-TO92-CBE")
      (footprint "eagle-import:TO92-CBE")
      (libsource (lib "eagle-import") (part "-NPN-TO92-CBEMPS2222A"))
    )
    (comp (ref "T64")
      (value "MPS2222A-NPN-TO92-CBE")
      (footprint "eagle-import:TO92-CBE")
      (libsource (lib "eagle-import") (part "-NPN-TO92-CBEMPS2222A"))
    )
    (comp (ref "T65")
      (value "MPS2222A-NPN-TO92-CBE")
      (footprint "eagle-import:TO92-CBE")
      (libsource (lib "eagle-import") (part "-NPN-TO92-CBEMPS2222A"))
    )
    (comp (ref "T66")
      (value "MPS2222A-NPN-TO92-CBE")
      (footprint "eagle-import:TO92-CBE")
      (libsource (lib "eagle-import") (part "-NPN-TO92-CBEMPS2222A"))
    )
    (comp (ref "T67")
      (value "MPS2222A-NPN-TO92-CBE")
      (footprint "eagle-import:TO92-CBE")
      (libsource (lib "eagle-import") (part "-NPN-TO92-CBEMPS2222A"))
    )
    (comp (ref "T68")
      (value "MPS2222A-NPN-TO92-CBE")
      (footprint "eagle-import:TO92-CBE")
      (libsource (lib "eagle-import") (part "-NPN-TO92-CBEMPS2222A"))
    )
    (comp (ref "T69")
      (value "MPS2222A-NPN-TO92-CBE")
      (footprint "eagle-import:TO92-CBE")
      (libsource (lib "eagle-import") (part "-NPN-TO92-CBEMPS2222A"))
    )
    (comp (ref "T70")
      (value "MPS2222A-NPN-TO92-CBE")
      (footprint "eagle-import:TO92-CBE")
      (libsource (lib "eagle-import") (part "-NPN-TO92-CBEMPS2222A"))
    )
    (comp (ref "T71")
      (value "MPS2222A-NPN-TO92-CBE")
      (footprint "eagle-import:TO92-CBE")
      (libsource (lib "eagle-import") (part "-NPN-TO92-CBEMPS2222A"))
    )
    (comp (ref "T72")
      (value "MPS2222A-NPN-TO92-CBE")
      (footprint "eagle-import:TO92-CBE")
      (libsource (lib "eagle-import") (part "-NPN-TO92-CBEMPS2222A"))
    )
    (comp (ref "T73")
      (value "MPS2222A-NPN-TO92-CBE")
      (footprint "eagle-import:TO92-CBE")
      (libsource (lib "eagle-import") (part "-NPN-TO92-CBEMPS2222A"))
    )
    (comp (ref "T74")
      (value "MPS2222A-NPN-TO92-CBE")
      (footprint "eagle-import:TO92-CBE")
      (libsource (lib "eagle-import") (part "-NPN-TO92-CBEMPS2222A"))
    )
    (comp (ref "T75")
      (value "MPS2222A-NPN-TO92-CBE")
      (footprint "eagle-import:TO92-CBE")
      (libsource (lib "eagle-import") (part "-NPN-TO92-CBEMPS2222A"))
    )
    (comp (ref "T76")
      (value "MPS2222A-NPN-TO92-CBE")
      (footprint "eagle-import:TO92-CBE")
      (libsource (lib "eagle-import") (part "-NPN-TO92-CBEMPS2222A"))
    )
    (comp (ref "T77")
      (value "MPS2222A-NPN-TO92-CBE")
      (footprint "eagle-import:TO92-CBE")
      (libsource (lib "eagle-import") (part "-NPN-TO92-CBEMPS2222A"))
    )
    (comp (ref "T78")
      (value "MPS2222A-NPN-TO92-CBE")
      (footprint "eagle-import:TO92-CBE")
      (libsource (lib "eagle-import") (part "-NPN-TO92-CBEMPS2222A"))
    )
    (comp (ref "T79")
      (value "MPS2222A-NPN-TO92-CBE")
      (footprint "eagle-import:TO92-CBE")
      (libsource (lib "eagle-import") (part "-NPN-TO92-CBEMPS2222A"))
    )
    (comp (ref "T80")
      (value "MPS2222A-NPN-TO92-CBE")
      (footprint "eagle-import:TO92-CBE")
      (libsource (lib "eagle-import") (part "-NPN-TO92-CBEMPS2222A"))
    )
    (comp (ref "T81")
      (value "MPS2222A-NPN-TO92-CBE")
      (footprint "eagle-import:TO92-CBE")
      (libsource (lib "eagle-import") (part "-NPN-TO92-CBEMPS2222A"))
    )
    (comp (ref "T82")
      (value "MPS2222A-NPN-TO92-CBE")
      (footprint "eagle-import:TO92-CBE")
      (libsource (lib "eagle-import") (part "-NPN-TO92-CBEMPS2222A"))
    )
    (comp (ref "T83")
      (value "MPS2222A-NPN-TO92-CBE")
      (footprint "eagle-import:TO92-CBE")
      (libsource (lib "eagle-import") (part "-NPN-TO92-CBEMPS2222A"))
    )
    (comp (ref "T84")
      (value "MPS2222A-NPN-TO92-CBE")
      (footprint "eagle-import:TO92-CBE")
      (libsource (lib "eagle-import") (part "-NPN-TO92-CBEMPS2222A"))
    )
    (comp (ref "T85")
      (value "MPS2222A-NPN-TO92-CBE")
      (footprint "eagle-import:TO92-CBE")
      (libsource (lib "eagle-import") (part "-NPN-TO92-CBEMPS2222A"))
    )
    (comp (ref "T86")
      (value "MPS2222A-NPN-TO92-CBE")
      (footprint "eagle-import:TO92-CBE")
      (libsource (lib "eagle-import") (part "-NPN-TO92-CBEMPS2222A"))
    )
    (comp (ref "T87")
      (value "MPS2222A-NPN-TO92-CBE")
      (footprint "eagle-import:TO92-CBE")
      (libsource (lib "eagle-import") (part "-NPN-TO92-CBEMPS2222A"))
    )
    (comp (ref "T88")
      (value "MPS2222A-NPN-TO92-CBE")
      (footprint "eagle-import:TO92-CBE")
      (libsource (lib "eagle-import") (part "-NPN-TO92-CBEMPS2222A"))
    )
    (comp (ref "T89")
      (value "MPS2222A-NPN-TO92-CBE")
      (footprint "eagle-import:TO92-CBE")
      (libsource (lib "eagle-import") (part "-NPN-TO92-CBEMPS2222A"))
    )
    (comp (ref "TAD")
      (value "BULB")
      (footprint "eagle-import:BULB")
      (libsource (lib "eagle-import") (part "BULB"))
    )
    (comp (ref "WORDCOUNT")
      (value "BULB")
      (footprint "eagle-import:BULB")
      (libsource (lib "eagle-import") (part "BULB"))
    )
  )
  (nets
    (net (code "1") (name "+15V") (class "Default")
      (node (ref "+V1") (pin "1") (pinfunction "1_1") (pintype "passive"))
      (node (ref "+V2") (pin "1") (pinfunction "1_1") (pintype "passive"))
      (node (ref "+V3") (pin "1") (pinfunction "1_1") (pintype "passive"))
      (node (ref "R1") (pin "1") (pinfunction "1_1") (pintype "passive"))
      (node (ref "R10") (pin "1") (pinfunction "1_1") (pintype "passive"))
      (node (ref "R11") (pin "1") (pinfunction "1_1") (pintype "passive"))
      (node (ref "R12") (pin "1") (pinfunction "1_1") (pintype "passive"))
      (node (ref "R13") (pin "1") (pinfunction "1_1") (pintype "passive"))
      (node (ref "R14") (pin "1") (pinfunction "1_1") (pintype "passive"))
      (node (ref "R15") (pin "1") (pinfunction "1_1") (pintype "passive"))
      (node (ref "R16") (pin "1") (pinfunction "1_1") (pintype "passive"))
      (node (ref "R17") (pin "1") (pinfunction "1_1") (pintype "passive"))
      (node (ref "R18") (pin "1") (pinfunction "1_1") (pintype "passive"))
      (node (ref "R19") (pin "1") (pinfunction "1_1") (pintype "passive"))
      (node (ref "R2") (pin "1") (pinfunction "1_1") (pintype "passive"))
      (node (ref "R20") (pin "1") (pinfunction "1_1") (pintype "passive"))
      (node (ref "R21") (pin "1") (pinfunction "1_1") (pintype "passive"))
      (node (ref "R22") (pin "1") (pinfunction "1_1") (pintype "passive"))
      (node (ref "R23") (pin "1") (pinfunction "1_1") (pintype "passive"))
      (node (ref "R24") (pin "1") (pinfunction "1_1") (pintype "passive"))
      (node (ref "R25") (pin "1") (pinfunction "1_1") (pintype "passive"))
      (node (ref "R26") (pin "1") (pinfunction "1_1") (pintype "passive"))
      (node (ref "R27") (pin "1") (pinfunction "1_1") (pintype "passive"))
      (node (ref "R28") (pin "1") (pinfunction "1_1") (pintype "passive"))
      (node (ref "R29") (pin "1") (pinfunction "1_1") (pintype "passive"))
      (node (ref "R3") (pin "1") (pinfunction "1_1") (pintype "passive"))
      (node (ref "R30") (pin "1") (pinfunction "1_1") (pintype "passive"))
      (node (ref "R31") (pin "1") (pinfunction "1_1") (pintype "passive"))
      (node (ref "R32") (pin "1") (pinfunction "1_1") (pintype "passive"))
      (node (ref "R33") (pin "1") (pinfunction "1_1") (pintype "passive"))
      (node (ref "R34") (pin "1") (pinfunction "1_1") (pintype "passive"))
      (node (ref "R35") (pin "1") (pinfunction "1_1") (pintype "passive"))
      (node (ref "R36") (pin "1") (pinfunction "1_1") (pintype "passive"))
      (node (ref "R37") (pin "1") (pinfunction "1_1") (pintype "passive"))
      (node (ref "R38") (pin "1") (pinfunction "1_1") (pintype "passive"))
      (node (ref "R39") (pin "1") (pinfunction "1_1") (pintype "passive"))
      (node (ref "R4") (pin "1") (pinfunction "1_1") (pintype "passive"))
      (node (ref "R40") (pin "1") (pinfunction "1_1") (pintype "passive"))
      (node (ref "R41") (pin "1") (pinfunction "1_1") (pintype "passive"))
      (node (ref "R42") (pin "1") (pinfunction "1_1") (pintype "passive"))
      (node (ref "R43") (pin "1") (pinfunction "1_1") (pintype "passive"))
      (node (ref "R44") (pin "1") (pinfunction "1_1") (pintype "passive"))
      (node (ref "R45") (pin "1") (pinfunction "1_1") (pintype "passive"))
      (node (ref "R46") (pin "1") (pinfunction "1_1") (pintype "passive"))
      (node (ref "R47") (pin "1") (pinfunction "1_1") (pintype "passive"))
      (node (ref "R48") (pin "1") (pinfunction "1_1") (pintype "passive"))
      (node (ref "R49") (pin "1") (pinfunction "1_1") (pintype "passive"))
      (node (ref "R5") (pin "1") (pinfunction "1_1") (pintype "passive"))
      (node (ref "R50") (pin "1") (pinfunction "1_1") (pintype "passive"))
      (node (ref "R51") (pin "1") (pinfunction "1_1") (pintype "passive"))
      (node (ref "R52") (pin "1") (pinfunction "1_1") (pintype "passive"))
      (node (ref "R53") (pin "1") (pinfunction "1_1") (pintype "passive"))
      (node (ref "R54") (pin "1") (pinfunction "1_1") (pintype "passive"))
      (node (ref "R55") (pin "1") (pinfunction "1_1") (pintype "passive"))
      (node (ref "R56") (pin "1") (pinfunction "1_1") (pintype "passive"))
      (node (ref "R57") (pin "1") (pinfunction "1_1") (pintype "passive"))
      (node (ref "R58") (pin "1") (pinfunction "1_1") (pintype "passive"))
      (node (ref "R59") (pin "1") (pinfunction "1_1") (pintype "passive"))
      (node (ref "R6") (pin "1") (pinfunction "1_1") (pintype "passive"))
      (node (ref "R60") (pin "1") (pinfunction "1_1") (pintype "passive"))
      (node (ref "R61") (pin "1") (pinfunction "1_1") (pintype "passive"))
      (node (ref "R62") (pin "1") (pinfunction "1_1") (pintype "passive"))
      (node (ref "R63") (pin "1") (pinfunction "1_1") (pintype "passive"))
      (node (ref "R64") (pin "1") (pinfunction "1_1") (pintype "passive"))
      (node (ref "R65") (pin "1") (pinfunction "1_1") (pintype "passive"))
      (node (ref "R66") (pin "1") (pinfunction "1_1") (pintype "passive"))
      (node (ref "R67") (pin "1") (pinfunction "1_1") (pintype "passive"))
      (node (ref "R68") (pin "1") (pinfunction "1_1") (pintype "passive"))
      (node (ref "R69") (pin "1") (pinfunction "1_1") (pintype "passive"))
      (node (ref "R7") (pin "1") (pinfunction "1_1") (pintype "passive"))
      (node (ref "R70") (pin "1") (pinfunction "1_1") (pintype "passive"))
      (node (ref "R71") (pin "1") (pinfunction "1_1") (pintype "passive"))
      (node (ref "R72") (pin "1") (pinfunction "1_1") (pintype "passive"))
      (node (ref "R73") (pin "1") (pinfunction "1_1") (pintype "passive"))
      (node (ref "R74") (pin "1") (pinfunction "1_1") (pintype "passive"))
      (node (ref "R75") (pin "1") (pinfunction "1_1") (pintype "passive"))
      (node (ref "R76") (pin "1") (pinfunction "1_1") (pintype "passive"))
      (node (ref "R77") (pin "1") (pinfunction "1_1") (pintype "passive"))
      (node (ref "R78") (pin "1") (pinfunction "1_1") (pintype "passive"))
      (node (ref "R79") (pin "1") (pinfunction "1_1") (pintype "passive"))
      (node (ref "R8") (pin "1") (pinfunction "1_1") (pintype "passive"))
      (node (ref "R80") (pin "1") (pinfunction "1_1") (pintype "passive"))
      (node (ref "R81") (pin "1") (pinfunction "1_1") (pintype "passive"))
      (node (ref "R82") (pin "1") (pinfunction "1_1") (pintype "passive"))
      (node (ref "R83") (pin "1") (pinfunction "1_1") (pintype "passive"))
      (node (ref "R84") (pin "1") (pinfunction "1_1") (pintype "passive"))
      (node (ref "R85") (pin "1") (pinfunction "1_1") (pintype "passive"))
      (node (ref "R86") (pin "1") (pinfunction "1_1") (pintype "passive"))
      (node (ref "R87") (pin "1") (pinfunction "1_1") (pintype "passive"))
      (node (ref "R88") (pin "1") (pinfunction "1_1") (pintype "passive"))
      (node (ref "R89") (pin "1") (pinfunction "1_1") (pintype "passive"))
      (node (ref "R9") (pin "1") (pinfunction "1_1") (pintype "passive"))
    )
    (net (code "2") (name "AC0") (class "Default")
      (node (ref "D40TOP") (pin "4") (pinfunction "1_4") (pintype "passive"))
      (node (ref "E40") (pin "7") (pinfunction "7_7") (pintype "passive"))
      (node (ref "T43") (pin "B") (pinfunction "B_B") (pintype "passive"))
    )
    (net (code "3") (name "AC1") (class "Default")
      (node (ref "D40BOT") (pin "2") (pinfunction "1_2") (pintype "passive"))
      (node (ref "E40") (pin "4") (pinfunction "4_4") (pintype "passive"))
      (node (ref "T44") (pin "B") (pinfunction "B_B") (pintype "passive"))
    )
    (net (code "4") (name "AC2") (class "Default")
      (node (ref "D40TOP") (pin "12") (pinfunction "1_12") (pintype "passive"))
      (node (ref "E40") (pin "21") (pinfunction "21_21") (pintype "passive"))
      (node (ref "T45") (pin "B") (pinfunction "B_B") (pintype "passive"))
    )
    (net (code "5") (name "AC3") (class "Default")
      (node (ref "D40BOT") (pin "9") (pinfunction "1_9") (pintype "passive"))
      (node (ref "E40") (pin "14") (pinfunction "14_14") (pintype "passive"))
      (node (ref "T46") (pin "B") (pinfunction "B_B") (pintype "passive"))
    )
    (net (code "6") (name "AC4") (class "Default")
      (node (ref "D40TOP") (pin "17") (pinfunction "1_17") (pintype "passive"))
      (node (ref "E40") (pin "31") (pinfunction "31_31") (pintype "passive"))
      (node (ref "T47") (pin "B") (pinfunction "B_B") (pintype "passive"))
    )
    (net (code "7") (name "AC5") (class "Default")
      (node (ref "D40BOT") (pin "16") (pinfunction "1_16") (pintype "passive"))
      (node (ref "E40") (pin "28") (pinfunction "28_28") (pintype "passive"))
      (node (ref "T48") (pin "B") (pinfunction "B_B") (pintype "passive"))
    )
    (net (code "8") (name "AC6") (class "Default")
      (node (ref "E40TOP") (pin "4") (pinfunction "1_4") (pintype "passive"))
      (node (ref "F40") (pin "7") (pinfunction "7_7") (pintype "passive"))
      (node (ref "T49") (pin "B") (pinfunction "B_B") (pintype "passive"))
    )
    (net (code "9") (name "AC7") (class "Default")
      (node (ref "E40BOT") (pin "2") (pinfunction "1_2") (pintype "passive"))
      (node (ref "F40") (pin "4") (pinfunction "4_4") (pintype "passive"))
      (node (ref "T50") (pin "B") (pinfunction "B_B") (pintype "passive"))
    )
    (net (code "10") (name "AC8") (class "Default")
      (node (ref "E40TOP") (pin "12") (pinfunction "1_12") (pintype "passive"))
      (node (ref "F40") (pin "21") (pinfunction "21_21") (pintype "passive"))
      (node (ref "T51") (pin "B") (pinfunction "B_B") (pintype "passive"))
    )
    (net (code "11") (name "AC9") (class "Default")
      (node (ref "E40BOT") (pin "9") (pinfunction "1_9") (pintype "passive"))
      (node (ref "F40") (pin "14") (pinfunction "14_14") (pintype "passive"))
      (node (ref "T52") (pin "B") (pinfunction "B_B") (pintype "passive"))
    )
    (net (code "12") (name "AC10") (class "Default")
      (node (ref "E40TOP") (pin "17") (pinfunction "1_17") (pintype "passive"))
      (node (ref "F40") (pin "31") (pinfunction "31_31") (pintype "passive"))
      (node (ref "T53") (pin "B") (pinfunction "B_B") (pintype "passive"))
    )
    (net (code "13") (name "AC11") (class "Default")
      (node (ref "E40BOT") (pin "16") (pinfunction "1_16") (pintype "passive"))
      (node (ref "F40") (pin "28") (pinfunction "28_28") (pintype "passive"))
      (node (ref "T54") (pin "B") (pinfunction "B_B") (pintype "passive"))
    )
    (net (code "14") (name "AND") (class "Default")
      (node (ref "D40") (pin "2") (pinfunction "2_2") (pintype "passive"))
      (node (ref "F40BOT") (pin "1") (pinfunction "1_1") (pintype "passive"))
      (node (ref "T82") (pin "B") (pinfunction "B_B") (pintype "passive"))
    )
    (net (code "15") (name "BREAK") (class "Default")
      (node (ref "D40") (pin "22") (pinfunction "22_22") (pintype "passive"))
      (node (ref "F40BOT") (pin "12") (pinfunction "1_12") (pintype "passive"))
      (node (ref "T81") (pin "B") (pinfunction "B_B") (pintype "passive"))
    )
    (net (code "16") (name "CA") (class "Default")
      (node (ref "D40") (pin "32") (pinfunction "32_32") (pintype "passive"))
      (node (ref "F40BOT") (pin "18") (pinfunction "1_18") (pintype "passive"))
      (node (ref "T80") (pin "B") (pinfunction "B_B") (pintype "passive"))
    )
    (net (code "17") (name "DCA") (class "Default")
      (node (ref "D40") (pin "8") (pinfunction "8_8") (pintype "passive"))
      (node (ref "F40BOT") (pin "4") (pinfunction "1_4") (pintype "passive"))
      (node (ref "T85") (pin "B") (pinfunction "B_B") (pintype "passive"))
    )
    (net (code "18") (name "DEFER") (class "Default")
      (node (ref "D40") (pin "28") (pinfunction "28_28") (pintype "passive"))
      (node (ref "F40BOT") (pin "16") (pinfunction "1_16") (pintype "passive"))
      (node (ref "T78") (pin "B") (pinfunction "B_B") (pintype "passive"))
    )
    (net (code "19") (name "DF0") (class "Default")
      (node (ref "C40") (pin "1") (pinfunction "1_1") (pintype "passive"))
      (node (ref "C40TOP") (pin "1") (pinfunction "1_1") (pintype "passive"))
      (node (ref "T1") (pin "B") (pinfunction "B_B") (pintype "passive"))
    )
    (net (code "20") (name "DF1") (class "Default")
      (node (ref "C40") (pin "10") (pinfunction "10_10") (pintype "passive"))
      (node (ref "C40BOT") (pin "5") (pinfunction "1_5") (pintype "passive"))
      (node (ref "T2") (pin "B") (pinfunction "B_B") (pintype "passive"))
    )
    (net (code "21") (name "DF2") (class "Default")
      (node (ref "C40") (pin "11") (pinfunction "11_11") (pintype "passive"))
      (node (ref "C40TOP") (pin "6") (pinfunction "1_6") (pintype "passive"))
      (node (ref "T3") (pin "B") (pinfunction "B_B") (pintype "passive"))
    )
    (net (code "22") (name "EXECUTE") (class "Default")
      (node (ref "D40") (pin "26") (pinfunction "26_26") (pintype "passive"))
      (node (ref "F40BOT") (pin "15") (pinfunction "1_15") (pintype "passive"))
      (node (ref "T77") (pin "B") (pinfunction "B_B") (pintype "passive"))
    )
    (net (code "23") (name "FETCH") (class "Default")
      (node (ref "D40") (pin "24") (pinfunction "24_24") (pintype "passive"))
      (node (ref "F40BOT") (pin "14") (pinfunction "1_14") (pintype "passive"))
      (node (ref "T76") (pin "B") (pinfunction "B_B") (pintype "passive"))
    )
    (net (code "24") (name "GND") (class "Default")
      (node (ref "GND1") (pin "1") (pinfunction "1_1") (pintype "passive"))
      (node (ref "GND2") (pin "1") (pinfunction "1_1") (pintype "passive"))
      (node (ref "GND3") (pin "1") (pinfunction "1_1") (pintype "passive"))
      (node (ref "T1") (pin "E") (pinfunction "E_E") (pintype "passive"))
      (node (ref "T10") (pin "E") (pinfunction "E_E") (pintype "passive"))
      (node (ref "T11") (pin "E") (pinfunction "E_E") (pintype "passive"))
      (node (ref "T12") (pin "E") (pinfunction "E_E") (pintype "passive"))
      (node (ref "T13") (pin "E") (pinfunction "E_E") (pintype "passive"))
      (node (ref "T14") (pin "E") (pinfunction "E_E") (pintype "passive"))
      (node (ref "T15") (pin "E") (pinfunction "E_E") (pintype "passive"))
      (node (ref "T16") (pin "E") (pinfunction "E_E") (pintype "passive"))
      (node (ref "T17") (pin "E") (pinfunction "E_E") (pintype "passive"))
      (node (ref "T18") (pin "E") (pinfunction "E_E") (pintype "passive"))
      (node (ref "T19") (pin "E") (pinfunction "E_E") (pintype "passive"))
      (node (ref "T2") (pin "E") (pinfunction "E_E") (pintype "passive"))
      (node (ref "T20") (pin "E") (pinfunction "E_E") (pintype "passive"))
      (node (ref "T21") (pin "E") (pinfunction "E_E") (pintype "passive"))
      (node (ref "T22") (pin "E") (pinfunction "E_E") (pintype "passive"))
      (node (ref "T23") (pin "E") (pinfunction "E_E") (pintype "passive"))
      (node (ref "T24") (pin "E") (pinfunction "E_E") (pintype "passive"))
      (node (ref "T25") (pin "E") (pinfunction "E_E") (pintype "passive"))
      (node (ref "T26") (pin "E") (pinfunction "E_E") (pintype "passive"))
      (node (ref "T27") (pin "E") (pinfunction "E_E") (pintype "passive"))
      (node (ref "T28") (pin "E") (pinfunction "E_E") (pintype "passive"))
      (node (ref "T29") (pin "E") (pinfunction "E_E") (pintype "passive"))
      (node (ref "T3") (pin "E") (pinfunction "E_E") (pintype "passive"))
      (node (ref "T30") (pin "E") (pinfunction "E_E") (pintype "passive"))
      (node (ref "T31") (pin "E") (pinfunction "E_E") (pintype "passive"))
      (node (ref "T32") (pin "E") (pinfunction "E_E") (pintype "passive"))
      (node (ref "T33") (pin "E") (pinfunction "E_E") (pintype "passive"))
      (node (ref "T34") (pin "E") (pinfunction "E_E") (pintype "passive"))
      (node (ref "T35") (pin "E") (pinfunction "E_E") (pintype "passive"))
      (node (ref "T36") (pin "E") (pinfunction "E_E") (pintype "passive"))
      (node (ref "T37") (pin "E") (pinfunction "E_E") (pintype "passive"))
      (node (ref "T38") (pin "E") (pinfunction "E_E") (pintype "passive"))
      (node (ref "T39") (pin "E") (pinfunction "E_E") (pintype "passive"))
      (node (ref "T4") (pin "E") (pinfunction "E_E") (pintype "passive"))
      (node (ref "T40") (pin "E") (pinfunction "E_E") (pintype "passive"))
      (node (ref "T41") (pin "E") (pinfunction "E_E") (pintype "passive"))
      (node (ref "T42") (pin "E") (pinfunction "E_E") (pintype "passive"))
      (node (ref "T43") (pin "E") (pinfunction "E_E") (pintype "passive"))
      (node (ref "T44") (pin "E") (pinfunction "E_E") (pintype "passive"))
      (node (ref "T45") (pin "E") (pinfunction "E_E") (pintype "passive"))
      (node (ref "T46") (pin "E") (pinfunction "E_E") (pintype "passive"))
      (node (ref "T47") (pin "E") (pinfunction "E_E") (pintype "passive"))
      (node (ref "T48") (pin "E") (pinfunction "E_E") (pintype "passive"))
      (node (ref "T49") (pin "E") (pinfunction "E_E") (pintype "passive"))
      (node (ref "T5") (pin "E") (pinfunction "E_E") (pintype "passive"))
      (node (ref "T50") (pin "E") (pinfunction "E_E") (pintype "passive"))
      (node (ref "T51") (pin "E") (pinfunction "E_E") (pintype "passive"))
      (node (ref "T52") (pin "E") (pinfunction "E_E") (pintype "passive"))
      (node (ref "T53") (pin "E") (pinfunction "E_E") (pintype "passive"))
      (node (ref "T54") (pin "E") (pinfunction "E_E") (pintype "passive"))
      (node (ref "T55") (pin "E") (pinfunction "E_E") (pintype "passive"))
      (node (ref "T56") (pin "E") (pinfunction "E_E") (pintype "passive"))
      (node (ref "T57") (pin "E") (pinfunction "E_E") (pintype "passive"))
      (node (ref "T58") (pin "E") (pinfunction "E_E") (pintype "passive"))
      (node (ref "T59") (pin "E") (pinfunction "E_E") (pintype "passive"))
      (node (ref "T6") (pin "E") (pinfunction "E_E") (pintype "passive"))
      (node (ref "T60") (pin "E") (pinfunction "E_E") (pintype "passive"))
      (node (ref "T61") (pin "E") (pinfunction "E_E") (pintype "passive"))
      (node (ref "T62") (pin "E") (pinfunction "E_E") (pintype "passive"))
      (node (ref "T63") (pin "E") (pinfunction "E_E") (pintype "passive"))
      (node (ref "T64") (pin "E") (pinfunction "E_E") (pintype "passive"))
      (node (ref "T65") (pin "E") (pinfunction "E_E") (pintype "passive"))
      (node (ref "T66") (pin "E") (pinfunction "E_E") (pintype "passive"))
      (node (ref "T67") (pin "E") (pinfunction "E_E") (pintype "passive"))
      (node (ref "T68") (pin "E") (pinfunction "E_E") (pintype "passive"))
      (node (ref "T69") (pin "E") (pinfunction "E_E") (pintype "passive"))
      (node (ref "T7") (pin "E") (pinfunction "E_E") (pintype "passive"))
      (node (ref "T70") (pin "E") (pinfunction "E_E") (pintype "passive"))
      (node (ref "T71") (pin "E") (pinfunction "E_E") (pintype "passive"))
      (node (ref "T72") (pin "E") (pinfunction "E_E") (pintype "passive"))
      (node (ref "T73") (pin "E") (pinfunction "E_E") (pintype "passive"))
      (node (ref "T74") (pin "E") (pinfunction "E_E") (pintype "passive"))
      (node (ref "T75") (pin "E") (pinfunction "E_E") (pintype "passive"))
      (node (ref "T76") (pin "E") (pinfunction "E_E") (pintype "passive"))
      (node (ref "T77") (pin "E") (pinfunction "E_E") (pintype "passive"))
      (node (ref "T78") (pin "E") (pinfunction "E_E") (pintype "passive"))
      (node (ref "T79") (pin "E") (pinfunction "E_E") (pintype "passive"))
      (node (ref "T8") (pin "E") (pinfunction "E_E") (pintype "passive"))
      (node (ref "T80") (pin "E") (pinfunction "E_E") (pintype "passive"))
      (node (ref "T81") (pin "E") (pinfunction "E_E") (pintype "passive"))
      (node (ref "T82") (pin "E") (pinfunction "E_E") (pintype "passive"))
      (node (ref "T83") (pin "E") (pinfunction "E_E") (pintype "passive"))
      (node (ref "T84") (pin "E") (pinfunction "E_E") (pintype "passive"))
      (node (ref "T85") (pin "E") (pinfunction "E_E") (pintype "passive"))
      (node (ref "T86") (pin "E") (pinfunction "E_E") (pintype "passive"))
      (node (ref "T87") (pin "E") (pinfunction "E_E") (pintype "passive"))
      (node (ref "T88") (pin "E") (pinfunction "E_E") (pintype "passive"))
      (node (ref "T89") (pin "E") (pinfunction "E_E") (pintype "passive"))
      (node (ref "T9") (pin "E") (pinfunction "E_E") (pintype "passive"))
    )
    (net (code "25") (name "IF0") (class "Default")
      (node (ref "C40") (pin "24") (pinfunction "24_24") (pintype "passive"))
      (node (ref "C40BOT") (pin "14") (pinfunction "1_14") (pintype "passive"))
      (node (ref "T4") (pin "B") (pinfunction "B_B") (pintype "passive"))
    )
    (net (code "26") (name "IF1") (class "Default")
      (node (ref "C40") (pin "25") (pinfunction "25_25") (pintype "passive"))
      (node (ref "C40TOP") (pin "14") (pinfunction "1_14") (pintype "passive"))
      (node (ref "T5") (pin "B") (pinfunction "B_B") (pintype "passive"))
    )
    (net (code "27") (name "IF2") (class "Default")
      (node (ref "C40") (pin "34") (pinfunction "34_34") (pintype "passive"))
      (node (ref "C40BOT") (pin "19") (pinfunction "1_19") (pintype "passive"))
      (node (ref "T6") (pin "B") (pinfunction "B_B") (pintype "passive"))
    )
    (net (code "28") (name "ION") (class "Default")
      (node (ref "D40") (pin "34") (pinfunction "34_34") (pintype "passive"))
      (node (ref "F40BOT") (pin "19") (pinfunction "1_19") (pintype "passive"))
      (node (ref "T73") (pin "B") (pinfunction "B_B") (pintype "passive"))
    )
    (net (code "29") (name "IOT") (class "Default")
      (node (ref "D40") (pin "14") (pinfunction "14_14") (pintype "passive"))
      (node (ref "F40BOT") (pin "9") (pinfunction "1_9") (pintype "passive"))
      (node (ref "T88") (pin "B") (pinfunction "B_B") (pintype "passive"))
    )
    (net (code "30") (name "ISZ") (class "Default")
      (node (ref "D40") (pin "6") (pinfunction "6_6") (pintype "passive"))
      (node (ref "F40BOT") (pin "3") (pinfunction "1_3") (pintype "passive"))
      (node (ref "T84") (pin "B") (pinfunction "B_B") (pintype "passive"))
    )
    (net (code "31") (name "JMP") (class "Default")
      (node (ref "D40") (pin "12") (pinfunction "12_12") (pintype "passive"))
      (node (ref "F40BOT") (pin "6") (pinfunction "1_6") (pintype "passive"))
      (node (ref "T87") (pin "B") (pinfunction "B_B") (pintype "passive"))
    )
    (net (code "32") (name "JMS") (class "Default")
      (node (ref "D40") (pin "10") (pinfunction "10_10") (pintype "passive"))
      (node (ref "F40BOT") (pin "5") (pinfunction "1_5") (pintype "passive"))
      (node (ref "T86") (pin "B") (pinfunction "B_B") (pintype "passive"))
    )
    (net (code "33") (name "LINK") (class "Default")
      (node (ref "C40") (pin "28") (pinfunction "28_28") (pintype "passive"))
      (node (ref "C40BOT") (pin "16") (pinfunction "1_16") (pintype "passive"))
      (node (ref "T72") (pin "B") (pinfunction "B_B") (pintype "passive"))
    )
    (net (code "34") (name "MA0") (class "Default")
      (node (ref "D40TOP") (pin "2") (pinfunction "1_2") (pintype "passive"))
      (node (ref "E40") (pin "3") (pinfunction "3_3") (pintype "passive"))
      (node (ref "T19") (pin "B") (pinfunction "B_B") (pintype "passive"))
    )
    (net (code "35") (name "MA1") (class "Default")
      (node (ref "D40BOT") (pin "4") (pinfunction "1_4") (pintype "passive"))
      (node (ref "E40") (pin "8") (pinfunction "8_8") (pintype "passive"))
      (node (ref "T20") (pin "B") (pinfunction "B_B") (pintype "passive"))
    )
    (net (code "36") (name "MA2") (class "Default")
      (node (ref "D40TOP") (pin "7") (pinfunction "1_7") (pintype "passive"))
      (node (ref "E40") (pin "13") (pinfunction "13_13") (pintype "passive"))
      (node (ref "T21") (pin "B") (pinfunction "B_B") (pintype "passive"))
    )
    (net (code "37") (name "MA3") (class "Default")
      (node (ref "D40BOT") (pin "12") (pinfunction "1_12") (pintype "passive"))
      (node (ref "E40") (pin "22") (pinfunction "22_22") (pintype "passive"))
      (node (ref "T22") (pin "B") (pinfunction "B_B") (pintype "passive"))
    )
    (net (code "38") (name "MA4") (class "Default")
      (node (ref "D40TOP") (pin "15") (pinfunction "1_15") (pintype "passive"))
      (node (ref "E40") (pin "27") (pinfunction "27_27") (pintype "passive"))
      (node (ref "T23") (pin "B") (pinfunction "B_B") (pintype "passive"))
    )
    (net (code "39") (name "MA5") (class "Default")
      (node (ref "D40BOT") (pin "18") (pinfunction "1_18") (pintype "passive"))
      (node (ref "E40") (pin "32") (pinfunction "32_32") (pintype "passive"))
      (node (ref "T24") (pin "B") (pinfunction "B_B") (pintype "passive"))
    )
    (net (code "40") (name "MA6") (class "Default")
      (node (ref "E40TOP") (pin "2") (pinfunction "1_2") (pintype "passive"))
      (node (ref "F40") (pin "3") (pinfunction "3_3") (pintype "passive"))
      (node (ref "T25") (pin "B") (pinfunction "B_B") (pintype "passive"))
    )
    (net (code "41") (name "MA7") (class "Default")
      (node (ref "E40BOT") (pin "4") (pinfunction "1_4") (pintype "passive"))
      (node (ref "F40") (pin "8") (pinfunction "8_8") (pintype "passive"))
      (node (ref "T26") (pin "B") (pinfunction "B_B") (pintype "passive"))
    )
    (net (code "42") (name "MA8") (class "Default")
      (node (ref "E40TOP") (pin "7") (pinfunction "1_7") (pintype "passive"))
      (node (ref "F40") (pin "13") (pinfunction "13_13") (pintype "passive"))
      (node (ref "T27") (pin "B") (pinfunction "B_B") (pintype "passive"))
    )
    (net (code "43") (name "MA9") (class "Default")
      (node (ref "E40BOT") (pin "12") (pinfunction "1_12") (pintype "passive"))
      (node (ref "F40") (pin "22") (pinfunction "22_22") (pintype "passive"))
      (node (ref "T28") (pin "B") (pinfunction "B_B") (pintype "passive"))
    )
    (net (code "44") (name "MA10") (class "Default")
      (node (ref "E40TOP") (pin "15") (pinfunction "1_15") (pintype "passive"))
      (node (ref "F40") (pin "27") (pinfunction "27_27") (pintype "passive"))
      (node (ref "T29") (pin "B") (pinfunction "B_B") (pintype "passive"))
    )
    (net (code "45") (name "MA11") (class "Default")
      (node (ref "E40BOT") (pin "18") (pinfunction "1_18") (pintype "passive"))
      (node (ref "F40") (pin "32") (pinfunction "32_32") (pintype "passive"))
      (node (ref "T30") (pin "B") (pinfunction "B_B") (pintype "passive"))
    )
    (net (code "46") (name "MB0") (class "Default")
      (node (ref "D40TOP") (pin "3") (pinfunction "1_3") (pintype "passive"))
      (node (ref "E40") (pin "5") (pinfunction "5_5") (pintype "passive"))
      (node (ref "T31") (pin "B") (pinfunction "B_B") (pintype "passive"))
    )
    (net (code "47") (name "MB1") (class "Default")
      (node (ref "D40BOT") (pin "3") (pinfunction "1_3") (pintype "passive"))
      (node (ref "E40") (pin "6") (pinfunction "6_6") (pintype "passive"))
      (node (ref "T32") (pin "B") (pinfunction "B_B") (pintype "passive"))
    )
    (net (code "48") (name "MB2") (class "Default")
      (node (ref "D40TOP") (pin "8") (pinfunction "1_8") (pintype "passive"))
      (node (ref "E40") (pin "15") (pinfunction "15_15") (pintype "passive"))
      (node (ref "T33") (pin "B") (pinfunction "B_B") (pintype "passive"))
    )
    (net (code "49") (name "MB3") (class "Default")
      (node (ref "D40BOT") (pin "11") (pinfunction "1_11") (pintype "passive"))
      (node (ref "E40") (pin "16") (pinfunction "16_16") (pintype "passive"))
      (node (ref "T34") (pin "B") (pinfunction "B_B") (pintype "passive"))
    )
    (net (code "50") (name "MB4") (class "Default")
      (node (ref "D40TOP") (pin "16") (pinfunction "1_16") (pintype "passive"))
      (node (ref "E40") (pin "29") (pinfunction "29_29") (pintype "passive"))
      (node (ref "T35") (pin "B") (pinfunction "B_B") (pintype "passive"))
    )
    (net (code "51") (name "MB5") (class "Default")
      (node (ref "D40BOT") (pin "17") (pinfunction "1_17") (pintype "passive"))
      (node (ref "E40") (pin "30") (pinfunction "30_30") (pintype "passive"))
      (node (ref "T36") (pin "B") (pinfunction "B_B") (pintype "passive"))
    )
    (net (code "52") (name "MB6") (class "Default")
      (node (ref "E40TOP") (pin "3") (pinfunction "1_3") (pintype "passive"))
      (node (ref "F40") (pin "5") (pinfunction "5_5") (pintype "passive"))
      (node (ref "T37") (pin "B") (pinfunction "B_B") (pintype "passive"))
    )
    (net (code "53") (name "MB7") (class "Default")
      (node (ref "E40BOT") (pin "3") (pinfunction "1_3") (pintype "passive"))
      (node (ref "F40") (pin "6") (pinfunction "6_6") (pintype "passive"))
      (node (ref "T38") (pin "B") (pinfunction "B_B") (pintype "passive"))
    )
    (net (code "54") (name "MB8") (class "Default")
      (node (ref "E40TOP") (pin "8") (pinfunction "1_8") (pintype "passive"))
      (node (ref "F40") (pin "15") (pinfunction "15_15") (pintype "passive"))
      (node (ref "T39") (pin "B") (pinfunction "B_B") (pintype "passive"))
    )
    (net (code "55") (name "MB9") (class "Default")
      (node (ref "E40BOT") (pin "11") (pinfunction "1_11") (pintype "passive"))
      (node (ref "F40") (pin "16") (pinfunction "16_16") (pintype "passive"))
      (node (ref "T40") (pin "B") (pinfunction "B_B") (pintype "passive"))
    )
    (net (code "56") (name "MB10") (class "Default")
      (node (ref "E40TOP") (pin "16") (pinfunction "1_16") (pintype "passive"))
      (node (ref "F40") (pin "29") (pinfunction "29_29") (pintype "passive"))
      (node (ref "T41") (pin "B") (pinfunction "B_B") (pintype "passive"))
    )
    (net (code "57") (name "MB11") (class "Default")
      (node (ref "E40BOT") (pin "17") (pinfunction "1_17") (pintype "passive"))
      (node (ref "F40") (pin "30") (pinfunction "30_30") (pintype "passive"))
      (node (ref "T42") (pin "B") (pinfunction "B_B") (pintype "passive"))
    )
    (net (code "58") (name "MQ0") (class "Default")
      (node (ref "D40TOP") (pin "5") (pinfunction "1_5") (pintype "passive"))
      (node (ref "E40") (pin "9") (pinfunction "9_9") (pintype "passive"))
      (node (ref "T55") (pin "B") (pinfunction "B_B") (pintype "passive"))
    )
    (net (code "59") (name "MQ1") (class "Default")
      (node (ref "D40BOT") (pin "1") (pinfunction "1_1") (pintype "passive"))
      (node (ref "E40") (pin "2") (pinfunction "2_2") (pintype "passive"))
      (node (ref "T56") (pin "B") (pinfunction "B_B") (pintype "passive"))
    )
    (net (code "60") (name "MQ2") (class "Default")
      (node (ref "D40TOP") (pin "13") (pinfunction "1_13") (pintype "passive"))
      (node (ref "E40") (pin "23") (pinfunction "23_23") (pintype "passive"))
      (node (ref "T57") (pin "B") (pinfunction "B_B") (pintype "passive"))
    )
    (net (code "61") (name "MQ3") (class "Default")
      (node (ref "D40BOT") (pin "6") (pinfunction "1_6") (pintype "passive"))
      (node (ref "E40") (pin "12") (pinfunction "12_12") (pintype "passive"))
      (node (ref "T58") (pin "B") (pinfunction "B_B") (pintype "passive"))
    )
    (net (code "62") (name "MQ4") (class "Default")
      (node (ref "D40TOP") (pin "18") (pinfunction "1_18") (pintype "passive"))
      (node (ref "E40") (pin "33") (pinfunction "33_33") (pintype "passive"))
      (node (ref "T59") (pin "B") (pinfunction "B_B") (pintype "passive"))
    )
    (net (code "63") (name "MQ5") (class "Default")
      (node (ref "D40BOT") (pin "15") (pinfunction "1_15") (pintype "passive"))
      (node (ref "E40") (pin "26") (pinfunction "26_26") (pintype "passive"))
      (node (ref "T60") (pin "B") (pinfunction "B_B") (pintype "passive"))
    )
    (net (code "64") (name "MQ6") (class "Default")
      (node (ref "E40TOP") (pin "5") (pinfunction "1_5") (pintype "passive"))
      (node (ref "F40") (pin "9") (pinfunction "9_9") (pintype "passive"))
      (node (ref "T61") (pin "B") (pinfunction "B_B") (pintype "passive"))
    )
    (net (code "65") (name "MQ7") (class "Default")
      (node (ref "E40BOT") (pin "1") (pinfunction "1_1") (pintype "passive"))
      (node (ref "F40") (pin "2") (pinfunction "2_2") (pintype "passive"))
      (node (ref "T62") (pin "B") (pinfunction "B_B") (pintype "passive"))
    )
    (net (code "66") (name "MQ8") (class "Default")
      (node (ref "E40TOP") (pin "13") (pinfunction "1_13") (pintype "passive"))
      (node (ref "F40") (pin "23") (pinfunction "23_23") (pintype "passive"))
      (node (ref "T63") (pin "B") (pinfunction "B_B") (pintype "passive"))
    )
    (net (code "67") (name "MQ9") (class "Default")
      (node (ref "E40BOT") (pin "6") (pinfunction "1_6") (pintype "passive"))
      (node (ref "F40") (pin "12") (pinfunction "12_12") (pintype "passive"))
      (node (ref "T64") (pin "B") (pinfunction "B_B") (pintype "passive"))
    )
    (net (code "68") (name "MQ10") (class "Default")
      (node (ref "E40TOP") (pin "18") (pinfunction "1_18") (pintype "passive"))
      (node (ref "F40") (pin "33") (pinfunction "33_33") (pintype "passive"))
      (node (ref "T65") (pin "B") (pinfunction "B_B") (pintype "passive"))
    )
    (net (code "69") (name "MQ11") (class "Default")
      (node (ref "E40BOT") (pin "15") (pinfunction "1_15") (pintype "passive"))
      (node (ref "F40") (pin "26") (pinfunction "26_26") (pintype "passive"))
      (node (ref "T66") (pin "B") (pinfunction "B_B") (pintype "passive"))
    )
    (net (code "70") (name "Net-(AC0-PadA)") (class "Default")
      (node (ref "AC0") (pin "A") (pinfunction "A_A") (pintype "passive"))
      (node (ref "R43") (pin "2") (pinfunction "2_2") (pintype "passive"))
    )
    (net (code "71") (name "Net-(AC0-PadB)") (class "Default")
      (node (ref "AC0") (pin "B") (pinfunction "B_B") (pintype "passive"))
      (node (ref "T43") (pin "C") (pinfunction "C_C") (pintype "passive"))
    )
    (net (code "72") (name "Net-(AC1-PadA)") (class "Default")
      (node (ref "AC1") (pin "A") (pinfunction "A_A") (pintype "passive"))
      (node (ref "R44") (pin "2") (pinfunction "2_2") (pintype "passive"))
    )
    (net (code "73") (name "Net-(AC1-PadB)") (class "Default")
      (node (ref "AC1") (pin "B") (pinfunction "B_B") (pintype "passive"))
      (node (ref "T44") (pin "C") (pinfunction "C_C") (pintype "passive"))
    )
    (net (code "74") (name "Net-(AC2-PadA)") (class "Default")
      (node (ref "AC2") (pin "A") (pinfunction "A_A") (pintype "passive"))
      (node (ref "R45") (pin "2") (pinfunction "2_2") (pintype "passive"))
    )
    (net (code "75") (name "Net-(AC2-PadB)") (class "Default")
      (node (ref "AC2") (pin "B") (pinfunction "B_B") (pintype "passive"))
      (node (ref "T45") (pin "C") (pinfunction "C_C") (pintype "passive"))
    )
    (net (code "76") (name "Net-(AC3-PadA)") (class "Default")
      (node (ref "AC3") (pin "A") (pinfunction "A_A") (pintype "passive"))
      (node (ref "R46") (pin "2") (pinfunction "2_2") (pintype "passive"))
    )
    (net (code "77") (name "Net-(AC3-PadB)") (class "Default")
      (node (ref "AC3") (pin "B") (pinfunction "B_B") (pintype "passive"))
      (node (ref "T46") (pin "C") (pinfunction "C_C") (pintype "passive"))
    )
    (net (code "78") (name "Net-(AC4-PadA)") (class "Default")
      (node (ref "AC4") (pin "A") (pinfunction "A_A") (pintype "passive"))
      (node (ref "R47") (pin "2") (pinfunction "2_2") (pintype "passive"))
    )
    (net (code "79") (name "Net-(AC4-PadB)") (class "Default")
      (node (ref "AC4") (pin "B") (pinfunction "B_B") (pintype "passive"))
      (node (ref "T47") (pin "C") (pinfunction "C_C") (pintype "passive"))
    )
    (net (code "80") (name "Net-(AC5-PadA)") (class "Default")
      (node (ref "AC5") (pin "A") (pinfunction "A_A") (pintype "passive"))
      (node (ref "R48") (pin "2") (pinfunction "2_2") (pintype "passive"))
    )
    (net (code "81") (name "Net-(AC5-PadB)") (class "Default")
      (node (ref "AC5") (pin "B") (pinfunction "B_B") (pintype "passive"))
      (node (ref "T48") (pin "C") (pinfunction "C_C") (pintype "passive"))
    )
    (net (code "82") (name "Net-(AC6-PadA)") (class "Default")
      (node (ref "AC6") (pin "A") (pinfunction "A_A") (pintype "passive"))
      (node (ref "R49") (pin "2") (pinfunction "2_2") (pintype "passive"))
    )
    (net (code "83") (name "Net-(AC6-PadB)") (class "Default")
      (node (ref "AC6") (pin "B") (pinfunction "B_B") (pintype "passive"))
      (node (ref "T49") (pin "C") (pinfunction "C_C") (pintype "passive"))
    )
    (net (code "84") (name "Net-(AC7-PadA)") (class "Default")
      (node (ref "AC7") (pin "A") (pinfunction "A_A") (pintype "passive"))
      (node (ref "R50") (pin "2") (pinfunction "2_2") (pintype "passive"))
    )
    (net (code "85") (name "Net-(AC7-PadB)") (class "Default")
      (node (ref "AC7") (pin "B") (pinfunction "B_B") (pintype "passive"))
      (node (ref "T50") (pin "C") (pinfunction "C_C") (pintype "passive"))
    )
    (net (code "86") (name "Net-(AC8-PadA)") (class "Default")
      (node (ref "AC8") (pin "A") (pinfunction "A_A") (pintype "passive"))
      (node (ref "R51") (pin "2") (pinfunction "2_2") (pintype "passive"))
    )
    (net (code "87") (name "Net-(AC8-PadB)") (class "Default")
      (node (ref "AC8") (pin "B") (pinfunction "B_B") (pintype "passive"))
      (node (ref "T51") (pin "C") (pinfunction "C_C") (pintype "passive"))
    )
    (net (code "88") (name "Net-(AC9-PadA)") (class "Default")
      (node (ref "AC9") (pin "A") (pinfunction "A_A") (pintype "passive"))
      (node (ref "R52") (pin "2") (pinfunction "2_2") (pintype "passive"))
    )
    (net (code "89") (name "Net-(AC9-PadB)") (class "Default")
      (node (ref "AC9") (pin "B") (pinfunction "B_B") (pintype "passive"))
      (node (ref "T52") (pin "C") (pinfunction "C_C") (pintype "passive"))
    )
    (net (code "90") (name "Net-(AC10-PadA)") (class "Default")
      (node (ref "AC10") (pin "A") (pinfunction "A_A") (pintype "passive"))
      (node (ref "R53") (pin "2") (pinfunction "2_2") (pintype "passive"))
    )
    (net (code "91") (name "Net-(AC10-PadB)") (class "Default")
      (node (ref "AC10") (pin "B") (pinfunction "B_B") (pintype "passive"))
      (node (ref "T53") (pin "C") (pinfunction "C_C") (pintype "passive"))
    )
    (net (code "92") (name "Net-(AC11-PadA)") (class "Default")
      (node (ref "AC11") (pin "A") (pinfunction "A_A") (pintype "passive"))
      (node (ref "R54") (pin "2") (pinfunction "2_2") (pintype "passive"))
    )
    (net (code "93") (name "Net-(AC11-PadB)") (class "Default")
      (node (ref "AC11") (pin "B") (pinfunction "B_B") (pintype "passive"))
      (node (ref "T54") (pin "C") (pinfunction "C_C") (pintype "passive"))
    )
    (net (code "94") (name "Net-(AND-PadA)") (class "Default")
      (node (ref "AND") (pin "A") (pinfunction "A_A") (pintype "passive"))
      (node (ref "R82") (pin "2") (pinfunction "2_2") (pintype "passive"))
    )
    (net (code "95") (name "Net-(AND-PadB)") (class "Default")
      (node (ref "AND") (pin "B") (pinfunction "B_B") (pintype "passive"))
      (node (ref "T82") (pin "C") (pinfunction "C_C") (pintype "passive"))
    )
    (net (code "96") (name "Net-(BREAK-PadA)") (class "Default")
      (node (ref "BREAK") (pin "A") (pinfunction "A_A") (pintype "passive"))
      (node (ref "R81") (pin "2") (pinfunction "2_2") (pintype "passive"))
    )
    (net (code "97") (name "Net-(BREAK-PadB)") (class "Default")
      (node (ref "BREAK") (pin "B") (pinfunction "B_B") (pintype "passive"))
      (node (ref "T81") (pin "C") (pinfunction "C_C") (pintype "passive"))
    )
    (net (code "98") (name "Net-(CURRENTADDRESS-PadA)") (class "Default")
      (node (ref "CURRENTADDRESS") (pin "A") (pinfunction "A_A") (pintype "passive"))
      (node (ref "R80") (pin "2") (pinfunction "2_2") (pintype "passive"))
    )
    (net (code "99") (name "Net-(CURRENTADDRESS-PadB)") (class "Default")
      (node (ref "CURRENTADDRESS") (pin "B") (pinfunction "B_B") (pintype "passive"))
      (node (ref "T80") (pin "C") (pinfunction "C_C") (pintype "passive"))
    )
    (net (code "100") (name "Net-(DCA-PadA)") (class "Default")
      (node (ref "DCA") (pin "A") (pinfunction "A_A") (pintype "passive"))
      (node (ref "R85") (pin "2") (pinfunction "2_2") (pintype "passive"))
    )
    (net (code "101") (name "Net-(DCA-PadB)") (class "Default")
      (node (ref "DCA") (pin "B") (pinfunction "B_B") (pintype "passive"))
      (node (ref "T85") (pin "C") (pinfunction "C_C") (pintype "passive"))
    )
    (net (code "102") (name "Net-(DEFER-PadA)") (class "Default")
      (node (ref "DEFER") (pin "A") (pinfunction "A_A") (pintype "passive"))
      (node (ref "R78") (pin "2") (pinfunction "2_2") (pintype "passive"))
    )
    (net (code "103") (name "Net-(DEFER-PadB)") (class "Default")
      (node (ref "DEFER") (pin "B") (pinfunction "B_B") (pintype "passive"))
      (node (ref "T78") (pin "C") (pinfunction "C_C") (pintype "passive"))
    )
    (net (code "104") (name "Net-(DF0-PadA)") (class "Default")
      (node (ref "DF0") (pin "A") (pinfunction "A_A") (pintype "passive"))
      (node (ref "R1") (pin "2") (pinfunction "2_2") (pintype "passive"))
    )
    (net (code "105") (name "Net-(DF0-PadB)") (class "Default")
      (node (ref "DF0") (pin "B") (pinfunction "B_B") (pintype "passive"))
      (node (ref "T1") (pin "C") (pinfunction "C_C") (pintype "passive"))
    )
    (net (code "106") (name "Net-(DF1-PadA)") (class "Default")
      (node (ref "DF1") (pin "A") (pinfunction "A_A") (pintype "passive"))
      (node (ref "R2") (pin "2") (pinfunction "2_2") (pintype "passive"))
    )
    (net (code "107") (name "Net-(DF1-PadB)") (class "Default")
      (node (ref "DF1") (pin "B") (pinfunction "B_B") (pintype "passive"))
      (node (ref "T2") (pin "C") (pinfunction "C_C") (pintype "passive"))
    )
    (net (code "108") (name "Net-(DF2-PadA)") (class "Default")
      (node (ref "DF2") (pin "A") (pinfunction "A_A") (pintype "passive"))
      (node (ref "R3") (pin "2") (pinfunction "2_2") (pintype "passive"))
    )
    (net (code "109") (name "Net-(DF2-PadB)") (class "Default")
      (node (ref "DF2") (pin "B") (pinfunction "B_B") (pintype "passive"))
      (node (ref "T3") (pin "C") (pinfunction "C_C") (pintype "passive"))
    )
    (net (code "110") (name "Net-(EXECUTE-PadA)") (class "Default")
      (node (ref "EXECUTE") (pin "A") (pinfunction "A_A") (pintype "passive"))
      (node (ref "R77") (pin "2") (pinfunction "2_2") (pintype "passive"))
    )
    (net (code "111") (name "Net-(EXECUTE-PadB)") (class "Default")
      (node (ref "EXECUTE") (pin "B") (pinfunction "B_B") (pintype "passive"))
      (node (ref "T77") (pin "C") (pinfunction "C_C") (pintype "passive"))
    )
    (net (code "112") (name "Net-(FETCH-PadA)") (class "Default")
      (node (ref "FETCH") (pin "A") (pinfunction "A_A") (pintype "passive"))
      (node (ref "R76") (pin "2") (pinfunction "2_2") (pintype "passive"))
    )
    (net (code "113") (name "Net-(FETCH-PadB)") (class "Default")
      (node (ref "FETCH") (pin "B") (pinfunction "B_B") (pintype "passive"))
      (node (ref "T76") (pin "C") (pinfunction "C_C") (pintype "passive"))
    )
    (net (code "114") (name "Net-(IF0-PadA)") (class "Default")
      (node (ref "IF0") (pin "A") (pinfunction "A_A") (pintype "passive"))
      (node (ref "R4") (pin "2") (pinfunction "2_2") (pintype "passive"))
    )
    (net (code "115") (name "Net-(IF0-PadB)") (class "Default")
      (node (ref "IF0") (pin "B") (pinfunction "B_B") (pintype "passive"))
      (node (ref "T4") (pin "C") (pinfunction "C_C") (pintype "passive"))
    )
    (net (code "116") (name "Net-(IF1-PadA)") (class "Default")
      (node (ref "IF1") (pin "A") (pinfunction "A_A") (pintype "passive"))
      (node (ref "R5") (pin "2") (pinfunction "2_2") (pintype "passive"))
    )
    (net (code "117") (name "Net-(IF1-PadB)") (class "Default")
      (node (ref "IF1") (pin "B") (pinfunction "B_B") (pintype "passive"))
      (node (ref "T5") (pin "C") (pinfunction "C_C") (pintype "passive"))
    )
    (net (code "118") (name "Net-(IF2-PadA)") (class "Default")
      (node (ref "IF2") (pin "A") (pinfunction "A_A") (pintype "passive"))
      (node (ref "R6") (pin "2") (pinfunction "2_2") (pintype "passive"))
    )
    (net (code "119") (name "Net-(IF2-PadB)") (class "Default")
      (node (ref "IF2") (pin "B") (pinfunction "B_B") (pintype "passive"))
      (node (ref "T6") (pin "C") (pinfunction "C_C") (pintype "passive"))
    )
    (net (code "120") (name "Net-(ION-PadA)") (class "Default")
      (node (ref "ION") (pin "A") (pinfunction "A_A") (pintype "passive"))
      (node (ref "R73") (pin "2") (pinfunction "2_2") (pintype "passive"))
    )
    (net (code "121") (name "Net-(ION-PadB)") (class "Default")
      (node (ref "ION") (pin "B") (pinfunction "B_B") (pintype "passive"))
      (node (ref "T73") (pin "C") (pinfunction "C_C") (pintype "passive"))
    )
    (net (code "122") (name "Net-(IOT-PadA)") (class "Default")
      (node (ref "IOT") (pin "A") (pinfunction "A_A") (pintype "passive"))
      (node (ref "R88") (pin "2") (pinfunction "2_2") (pintype "passive"))
    )
    (net (code "123") (name "Net-(IOT-PadB)") (class "Default")
      (node (ref "IOT") (pin "B") (pinfunction "B_B") (pintype "passive"))
      (node (ref "T88") (pin "C") (pinfunction "C_C") (pintype "passive"))
    )
    (net (code "124") (name "Net-(ISZ-PadA)") (class "Default")
      (node (ref "ISZ") (pin "A") (pinfunction "A_A") (pintype "passive"))
      (node (ref "R84") (pin "2") (pinfunction "2_2") (pintype "passive"))
    )
    (net (code "125") (name "Net-(ISZ-PadB)") (class "Default")
      (node (ref "ISZ") (pin "B") (pinfunction "B_B") (pintype "passive"))
      (node (ref "T84") (pin "C") (pinfunction "C_C") (pintype "passive"))
    )
    (net (code "126") (name "Net-(JMP-PadA)") (class "Default")
      (node (ref "JMP") (pin "A") (pinfunction "A_A") (pintype "passive"))
      (node (ref "R87") (pin "2") (pinfunction "2_2") (pintype "passive"))
    )
    (net (code "127") (name "Net-(JMP-PadB)") (class "Default")
      (node (ref "JMP") (pin "B") (pinfunction "B_B") (pintype "passive"))
      (node (ref "T87") (pin "C") (pinfunction "C_C") (pintype "passive"))
    )
    (net (code "128") (name "Net-(JMS-PadA)") (class "Default")
      (node (ref "JMS") (pin "A") (pinfunction "A_A") (pintype "passive"))
      (node (ref "R86") (pin "2") (pinfunction "2_2") (pintype "passive"))
    )
    (net (code "129") (name "Net-(JMS-PadB)") (class "Default")
      (node (ref "JMS") (pin "B") (pinfunction "B_B") (pintype "passive"))
      (node (ref "T86") (pin "C") (pinfunction "C_C") (pintype "passive"))
    )
    (net (code "130") (name "Net-(LINK-PadA)") (class "Default")
      (node (ref "LINK") (pin "A") (pinfunction "A_A") (pintype "passive"))
      (node (ref "R72") (pin "2") (pinfunction "2_2") (pintype "passive"))
    )
    (net (code "131") (name "Net-(LINK-PadB)") (class "Default")
      (node (ref "LINK") (pin "B") (pinfunction "B_B") (pintype "passive"))
      (node (ref "T72") (pin "C") (pinfunction "C_C") (pintype "passive"))
    )
    (net (code "132") (name "Net-(MA0-PadA)") (class "Default")
      (node (ref "MA0") (pin "A") (pinfunction "A_A") (pintype "passive"))
      (node (ref "R19") (pin "2") (pinfunction "2_2") (pintype "passive"))
    )
    (net (code "133") (name "Net-(MA0-PadB)") (class "Default")
      (node (ref "MA0") (pin "B") (pinfunction "B_B") (pintype "passive"))
      (node (ref "T19") (pin "C") (pinfunction "C_C") (pintype "passive"))
    )
    (net (code "134") (name "Net-(MA1-PadA)") (class "Default")
      (node (ref "MA1") (pin "A") (pinfunction "A_A") (pintype "passive"))
      (node (ref "R20") (pin "2") (pinfunction "2_2") (pintype "passive"))
    )
    (net (code "135") (name "Net-(MA1-PadB)") (class "Default")
      (node (ref "MA1") (pin "B") (pinfunction "B_B") (pintype "passive"))
      (node (ref "T20") (pin "C") (pinfunction "C_C") (pintype "passive"))
    )
    (net (code "136") (name "Net-(MA2-PadA)") (class "Default")
      (node (ref "MA2") (pin "A") (pinfunction "A_A") (pintype "passive"))
      (node (ref "R21") (pin "2") (pinfunction "2_2") (pintype "passive"))
    )
    (net (code "137") (name "Net-(MA2-PadB)") (class "Default")
      (node (ref "MA2") (pin "B") (pinfunction "B_B") (pintype "passive"))
      (node (ref "T21") (pin "C") (pinfunction "C_C") (pintype "passive"))
    )
    (net (code "138") (name "Net-(MA3-PadA)") (class "Default")
      (node (ref "MA3") (pin "A") (pinfunction "A_A") (pintype "passive"))
      (node (ref "R22") (pin "2") (pinfunction "2_2") (pintype "passive"))
    )
    (net (code "139") (name "Net-(MA3-PadB)") (class "Default")
      (node (ref "MA3") (pin "B") (pinfunction "B_B") (pintype "passive"))
      (node (ref "T22") (pin "C") (pinfunction "C_C") (pintype "passive"))
    )
    (net (code "140") (name "Net-(MA4-PadA)") (class "Default")
      (node (ref "MA4") (pin "A") (pinfunction "A_A") (pintype "passive"))
      (node (ref "R23") (pin "2") (pinfunction "2_2") (pintype "passive"))
    )
    (net (code "141") (name "Net-(MA4-PadB)") (class "Default")
      (node (ref "MA4") (pin "B") (pinfunction "B_B") (pintype "passive"))
      (node (ref "T23") (pin "C") (pinfunction "C_C") (pintype "passive"))
    )
    (net (code "142") (name "Net-(MA5-PadA)") (class "Default")
      (node (ref "MA5") (pin "A") (pinfunction "A_A") (pintype "passive"))
      (node (ref "R24") (pin "2") (pinfunction "2_2") (pintype "passive"))
    )
    (net (code "143") (name "Net-(MA5-PadB)") (class "Default")
      (node (ref "MA5") (pin "B") (pinfunction "B_B") (pintype "passive"))
      (node (ref "T24") (pin "C") (pinfunction "C_C") (pintype "passive"))
    )
    (net (code "144") (name "Net-(MA6-PadA)") (class "Default")
      (node (ref "MA6") (pin "A") (pinfunction "A_A") (pintype "passive"))
      (node (ref "R25") (pin "2") (pinfunction "2_2") (pintype "passive"))
    )
    (net (code "145") (name "Net-(MA6-PadB)") (class "Default")
      (node (ref "MA6") (pin "B") (pinfunction "B_B") (pintype "passive"))
      (node (ref "T25") (pin "C") (pinfunction "C_C") (pintype "passive"))
    )
    (net (code "146") (name "Net-(MA7-PadA)") (class "Default")
      (node (ref "MA7") (pin "A") (pinfunction "A_A") (pintype "passive"))
      (node (ref "R26") (pin "2") (pinfunction "2_2") (pintype "passive"))
    )
    (net (code "147") (name "Net-(MA7-PadB)") (class "Default")
      (node (ref "MA7") (pin "B") (pinfunction "B_B") (pintype "passive"))
      (node (ref "T26") (pin "C") (pinfunction "C_C") (pintype "passive"))
    )
    (net (code "148") (name "Net-(MA8-PadA)") (class "Default")
      (node (ref "MA8") (pin "A") (pinfunction "A_A") (pintype "passive"))
      (node (ref "R27") (pin "2") (pinfunction "2_2") (pintype "passive"))
    )
    (net (code "149") (name "Net-(MA8-PadB)") (class "Default")
      (node (ref "MA8") (pin "B") (pinfunction "B_B") (pintype "passive"))
      (node (ref "T27") (pin "C") (pinfunction "C_C") (pintype "passive"))
    )
    (net (code "150") (name "Net-(MA9-PadA)") (class "Default")
      (node (ref "MA9") (pin "A") (pinfunction "A_A") (pintype "passive"))
      (node (ref "R28") (pin "2") (pinfunction "2_2") (pintype "passive"))
    )
    (net (code "151") (name "Net-(MA9-PadB)") (class "Default")
      (node (ref "MA9") (pin "B") (pinfunction "B_B") (pintype "passive"))
      (node (ref "T28") (pin "C") (pinfunction "C_C") (pintype "passive"))
    )
    (net (code "152") (name "Net-(MA10-PadA)") (class "Default")
      (node (ref "MA10") (pin "A") (pinfunction "A_A") (pintype "passive"))
      (node (ref "R29") (pin "2") (pinfunction "2_2") (pintype "passive"))
    )
    (net (code "153") (name "Net-(MA10-PadB)") (class "Default")
      (node (ref "MA10") (pin "B") (pinfunction "B_B") (pintype "passive"))
      (node (ref "T29") (pin "C") (pinfunction "C_C") (pintype "passive"))
    )
    (net (code "154") (name "Net-(MA11-PadA)") (class "Default")
      (node (ref "MA11") (pin "A") (pinfunction "A_A") (pintype "passive"))
      (node (ref "R30") (pin "2") (pinfunction "2_2") (pintype "passive"))
    )
    (net (code "155") (name "Net-(MA11-PadB)") (class "Default")
      (node (ref "MA11") (pin "B") (pinfunction "B_B") (pintype "passive"))
      (node (ref "T30") (pin "C") (pinfunction "C_C") (pintype "passive"))
    )
    (net (code "156") (name "Net-(MB0-PadA)") (class "Default")
      (node (ref "MB0") (pin "A") (pinfunction "A_A") (pintype "passive"))
      (node (ref "R31") (pin "2") (pinfunction "2_2") (pintype "passive"))
    )
    (net (code "157") (name "Net-(MB0-PadB)") (class "Default")
      (node (ref "MB0") (pin "B") (pinfunction "B_B") (pintype "passive"))
      (node (ref "T31") (pin "C") (pinfunction "C_C") (pintype "passive"))
    )
    (net (code "158") (name "Net-(MB1-PadA)") (class "Default")
      (node (ref "MB1") (pin "A") (pinfunction "A_A") (pintype "passive"))
      (node (ref "R32") (pin "2") (pinfunction "2_2") (pintype "passive"))
    )
    (net (code "159") (name "Net-(MB1-PadB)") (class "Default")
      (node (ref "MB1") (pin "B") (pinfunction "B_B") (pintype "passive"))
      (node (ref "T32") (pin "C") (pinfunction "C_C") (pintype "passive"))
    )
    (net (code "160") (name "Net-(MB2-PadA)") (class "Default")
      (node (ref "MB2") (pin "A") (pinfunction "A_A") (pintype "passive"))
      (node (ref "R33") (pin "2") (pinfunction "2_2") (pintype "passive"))
    )
    (net (code "161") (name "Net-(MB2-PadB)") (class "Default")
      (node (ref "MB2") (pin "B") (pinfunction "B_B") (pintype "passive"))
      (node (ref "T33") (pin "C") (pinfunction "C_C") (pintype "passive"))
    )
    (net (code "162") (name "Net-(MB3-PadA)") (class "Default")
      (node (ref "MB3") (pin "A") (pinfunction "A_A") (pintype "passive"))
      (node (ref "R34") (pin "2") (pinfunction "2_2") (pintype "passive"))
    )
    (net (code "163") (name "Net-(MB3-PadB)") (class "Default")
      (node (ref "MB3") (pin "B") (pinfunction "B_B") (pintype "passive"))
      (node (ref "T34") (pin "C") (pinfunction "C_C") (pintype "passive"))
    )
    (net (code "164") (name "Net-(MB4-PadA)") (class "Default")
      (node (ref "MB4") (pin "A") (pinfunction "A_A") (pintype "passive"))
      (node (ref "R35") (pin "2") (pinfunction "2_2") (pintype "passive"))
    )
    (net (code "165") (name "Net-(MB4-PadB)") (class "Default")
      (node (ref "MB4") (pin "B") (pinfunction "B_B") (pintype "passive"))
      (node (ref "T35") (pin "C") (pinfunction "C_C") (pintype "passive"))
    )
    (net (code "166") (name "Net-(MB5-PadA)") (class "Default")
      (node (ref "MB5") (pin "A") (pinfunction "A_A") (pintype "passive"))
      (node (ref "R36") (pin "2") (pinfunction "2_2") (pintype "passive"))
    )
    (net (code "167") (name "Net-(MB5-PadB)") (class "Default")
      (node (ref "MB5") (pin "B") (pinfunction "B_B") (pintype "passive"))
      (node (ref "T36") (pin "C") (pinfunction "C_C") (pintype "passive"))
    )
    (net (code "168") (name "Net-(MB6-PadA)") (class "Default")
      (node (ref "MB6") (pin "A") (pinfunction "A_A") (pintype "passive"))
      (node (ref "R37") (pin "2") (pinfunction "2_2") (pintype "passive"))
    )
    (net (code "169") (name "Net-(MB6-PadB)") (class "Default")
      (node (ref "MB6") (pin "B") (pinfunction "B_B") (pintype "passive"))
      (node (ref "T37") (pin "C") (pinfunction "C_C") (pintype "passive"))
    )
    (net (code "170") (name "Net-(MB7-PadA)") (class "Default")
      (node (ref "MB7") (pin "A") (pinfunction "A_A") (pintype "passive"))
      (node (ref "R38") (pin "2") (pinfunction "2_2") (pintype "passive"))
    )
    (net (code "171") (name "Net-(MB7-PadB)") (class "Default")
      (node (ref "MB7") (pin "B") (pinfunction "B_B") (pintype "passive"))
      (node (ref "T38") (pin "C") (pinfunction "C_C") (pintype "passive"))
    )
    (net (code "172") (name "Net-(MB8-PadA)") (class "Default")
      (node (ref "MB8") (pin "A") (pinfunction "A_A") (pintype "passive"))
      (node (ref "R39") (pin "2") (pinfunction "2_2") (pintype "passive"))
    )
    (net (code "173") (name "Net-(MB8-PadB)") (class "Default")
      (node (ref "MB8") (pin "B") (pinfunction "B_B") (pintype "passive"))
      (node (ref "T39") (pin "C") (pinfunction "C_C") (pintype "passive"))
    )
    (net (code "174") (name "Net-(MB9-PadA)") (class "Default")
      (node (ref "MB9") (pin "A") (pinfunction "A_A") (pintype "passive"))
      (node (ref "R40") (pin "2") (pinfunction "2_2") (pintype "passive"))
    )
    (net (code "175") (name "Net-(MB9-PadB)") (class "Default")
      (node (ref "MB9") (pin "B") (pinfunction "B_B") (pintype "passive"))
      (node (ref "T40") (pin "C") (pinfunction "C_C") (pintype "passive"))
    )
    (net (code "176") (name "Net-(MB10-PadA)") (class "Default")
      (node (ref "MB10") (pin "A") (pinfunction "A_A") (pintype "passive"))
      (node (ref "R41") (pin "2") (pinfunction "2_2") (pintype "passive"))
    )
    (net (code "177") (name "Net-(MB10-PadB)") (class "Default")
      (node (ref "MB10") (pin "B") (pinfunction "B_B") (pintype "passive"))
      (node (ref "T41") (pin "C") (pinfunction "C_C") (pintype "passive"))
    )
    (net (code "178") (name "Net-(MB11-PadA)") (class "Default")
      (node (ref "MB11") (pin "A") (pinfunction "A_A") (pintype "passive"))
      (node (ref "R42") (pin "2") (pinfunction "2_2") (pintype "passive"))
    )
    (net (code "179") (name "Net-(MB11-PadB)") (class "Default")
      (node (ref "MB11") (pin "B") (pinfunction "B_B") (pintype "passive"))
      (node (ref "T42") (pin "C") (pinfunction "C_C") (pintype "passive"))
    )
    (net (code "180") (name "Net-(MQ0-PadA)") (class "Default")
      (node (ref "MQ0") (pin "A") (pinfunction "A_A") (pintype "passive"))
      (node (ref "R55") (pin "2") (pinfunction "2_2") (pintype "passive"))
    )
    (net (code "181") (name "Net-(MQ0-PadB)") (class "Default")
      (node (ref "MQ0") (pin "B") (pinfunction "B_B") (pintype "passive"))
      (node (ref "T55") (pin "C") (pinfunction "C_C") (pintype "passive"))
    )
    (net (code "182") (name "Net-(MQ1-PadA)") (class "Default")
      (node (ref "MQ1") (pin "A") (pinfunction "A_A") (pintype "passive"))
      (node (ref "R56") (pin "2") (pinfunction "2_2") (pintype "passive"))
    )
    (net (code "183") (name "Net-(MQ1-PadB)") (class "Default")
      (node (ref "MQ1") (pin "B") (pinfunction "B_B") (pintype "passive"))
      (node (ref "T56") (pin "C") (pinfunction "C_C") (pintype "passive"))
    )
    (net (code "184") (name "Net-(MQ2-PadA)") (class "Default")
      (node (ref "MQ2") (pin "A") (pinfunction "A_A") (pintype "passive"))
      (node (ref "R57") (pin "2") (pinfunction "2_2") (pintype "passive"))
    )
    (net (code "185") (name "Net-(MQ2-PadB)") (class "Default")
      (node (ref "MQ2") (pin "B") (pinfunction "B_B") (pintype "passive"))
      (node (ref "T57") (pin "C") (pinfunction "C_C") (pintype "passive"))
    )
    (net (code "186") (name "Net-(MQ3-PadA)") (class "Default")
      (node (ref "MQ3") (pin "A") (pinfunction "A_A") (pintype "passive"))
      (node (ref "R58") (pin "2") (pinfunction "2_2") (pintype "passive"))
    )
    (net (code "187") (name "Net-(MQ3-PadB)") (class "Default")
      (node (ref "MQ3") (pin "B") (pinfunction "B_B") (pintype "passive"))
      (node (ref "T58") (pin "C") (pinfunction "C_C") (pintype "passive"))
    )
    (net (code "188") (name "Net-(MQ4-PadA)") (class "Default")
      (node (ref "MQ4") (pin "A") (pinfunction "A_A") (pintype "passive"))
      (node (ref "R59") (pin "2") (pinfunction "2_2") (pintype "passive"))
    )
    (net (code "189") (name "Net-(MQ4-PadB)") (class "Default")
      (node (ref "MQ4") (pin "B") (pinfunction "B_B") (pintype "passive"))
      (node (ref "T59") (pin "C") (pinfunction "C_C") (pintype "passive"))
    )
    (net (code "190") (name "Net-(MQ5-PadA)") (class "Default")
      (node (ref "MQ5") (pin "A") (pinfunction "A_A") (pintype "passive"))
      (node (ref "R60") (pin "2") (pinfunction "2_2") (pintype "passive"))
    )
    (net (code "191") (name "Net-(MQ5-PadB)") (class "Default")
      (node (ref "MQ5") (pin "B") (pinfunction "B_B") (pintype "passive"))
      (node (ref "T60") (pin "C") (pinfunction "C_C") (pintype "passive"))
    )
    (net (code "192") (name "Net-(MQ6-PadA)") (class "Default")
      (node (ref "MQ6") (pin "A") (pinfunction "A_A") (pintype "passive"))
      (node (ref "R61") (pin "2") (pinfunction "2_2") (pintype "passive"))
    )
    (net (code "193") (name "Net-(MQ6-PadB)") (class "Default")
      (node (ref "MQ6") (pin "B") (pinfunction "B_B") (pintype "passive"))
      (node (ref "T61") (pin "C") (pinfunction "C_C") (pintype "passive"))
    )
    (net (code "194") (name "Net-(MQ7-PadA)") (class "Default")
      (node (ref "MQ7") (pin "A") (pinfunction "A_A") (pintype "passive"))
      (node (ref "R62") (pin "2") (pinfunction "2_2") (pintype "passive"))
    )
    (net (code "195") (name "Net-(MQ7-PadB)") (class "Default")
      (node (ref "MQ7") (pin "B") (pinfunction "B_B") (pintype "passive"))
      (node (ref "T62") (pin "C") (pinfunction "C_C") (pintype "passive"))
    )
    (net (code "196") (name "Net-(MQ8-PadA)") (class "Default")
      (node (ref "MQ8") (pin "A") (pinfunction "A_A") (pintype "passive"))
      (node (ref "R63") (pin "2") (pinfunction "2_2") (pintype "passive"))
    )
    (net (code "197") (name "Net-(MQ8-PadB)") (class "Default")
      (node (ref "MQ8") (pin "B") (pinfunction "B_B") (pintype "passive"))
      (node (ref "T63") (pin "C") (pinfunction "C_C") (pintype "passive"))
    )
    (net (code "198") (name "Net-(MQ9-PadA)") (class "Default")
      (node (ref "MQ9") (pin "A") (pinfunction "A_A") (pintype "passive"))
      (node (ref "R64") (pin "2") (pinfunction "2_2") (pintype "passive"))
    )
    (net (code "199") (name "Net-(MQ9-PadB)") (class "Default")
      (node (ref "MQ9") (pin "B") (pinfunction "B_B") (pintype "passive"))
      (node (ref "T64") (pin "C") (pinfunction "C_C") (pintype "passive"))
    )
    (net (code "200") (name "Net-(MQ10-PadA)") (class "Default")
      (node (ref "MQ10") (pin "A") (pinfunction "A_A") (pintype "passive"))
      (node (ref "R65") (pin "2") (pinfunction "2_2") (pintype "passive"))
    )
    (net (code "201") (name "Net-(MQ10-PadB)") (class "Default")
      (node (ref "MQ10") (pin "B") (pinfunction "B_B") (pintype "passive"))
      (node (ref "T65") (pin "C") (pinfunction "C_C") (pintype "passive"))
    )
    (net (code "202") (name "Net-(MQ11-PadA)") (class "Default")
      (node (ref "MQ11") (pin "A") (pinfunction "A_A") (pintype "passive"))
      (node (ref "R66") (pin "2") (pinfunction "2_2") (pintype "passive"))
    )
    (net (code "203") (name "Net-(MQ11-PadB)") (class "Default")
      (node (ref "MQ11") (pin "B") (pinfunction "B_B") (pintype "passive"))
      (node (ref "T66") (pin "C") (pinfunction "C_C") (pintype "passive"))
    )
    (net (code "204") (name "Net-(OPR-PadA)") (class "Default")
      (node (ref "OPR") (pin "A") (pinfunction "A_A") (pintype "passive"))
      (node (ref "R89") (pin "2") (pinfunction "2_2") (pintype "passive"))
    )
    (net (code "205") (name "Net-(OPR-PadB)") (class "Default")
      (node (ref "OPR") (pin "B") (pinfunction "B_B") (pintype "passive"))
      (node (ref "T89") (pin "C") (pinfunction "C_C") (pintype "passive"))
    )
    (net (code "206") (name "Net-(PAUSE-PadA)") (class "Default")
      (node (ref "PAUSE") (pin "A") (pinfunction "A_A") (pintype "passive"))
      (node (ref "R74") (pin "2") (pinfunction "2_2") (pintype "passive"))
    )
    (net (code "207") (name "Net-(PAUSE-PadB)") (class "Default")
      (node (ref "PAUSE") (pin "B") (pinfunction "B_B") (pintype "passive"))
      (node (ref "T74") (pin "C") (pinfunction "C_C") (pintype "passive"))
    )
    (net (code "208") (name "Net-(PC0-PadA)") (class "Default")
      (node (ref "PC0") (pin "A") (pinfunction "A_A") (pintype "passive"))
      (node (ref "R7") (pin "2") (pinfunction "2_2") (pintype "passive"))
    )
    (net (code "209") (name "Net-(PC0-PadB)") (class "Default")
      (node (ref "PC0") (pin "B") (pinfunction "B_B") (pintype "passive"))
      (node (ref "T7") (pin "C") (pinfunction "C_C") (pintype "passive"))
    )
    (net (code "210") (name "Net-(PC1-PadA)") (class "Default")
      (node (ref "PC1") (pin "A") (pinfunction "A_A") (pintype "passive"))
      (node (ref "R8") (pin "2") (pinfunction "2_2") (pintype "passive"))
    )
    (net (code "211") (name "Net-(PC1-PadB)") (class "Default")
      (node (ref "PC1") (pin "B") (pinfunction "B_B") (pintype "passive"))
      (node (ref "T8") (pin "C") (pinfunction "C_C") (pintype "passive"))
    )
    (net (code "212") (name "Net-(PC2-PadA)") (class "Default")
      (node (ref "PC2") (pin "A") (pinfunction "A_A") (pintype "passive"))
      (node (ref "R9") (pin "2") (pinfunction "2_2") (pintype "passive"))
    )
    (net (code "213") (name "Net-(PC2-PadB)") (class "Default")
      (node (ref "PC2") (pin "B") (pinfunction "B_B") (pintype "passive"))
      (node (ref "T9") (pin "C") (pinfunction "C_C") (pintype "passive"))
    )
    (net (code "214") (name "Net-(PC3-PadA)") (class "Default")
      (node (ref "PC3") (pin "A") (pinfunction "A_A") (pintype "passive"))
      (node (ref "R10") (pin "2") (pinfunction "2_2") (pintype "passive"))
    )
    (net (code "215") (name "Net-(PC3-PadB)") (class "Default")
      (node (ref "PC3") (pin "B") (pinfunction "B_B") (pintype "passive"))
      (node (ref "T10") (pin "C") (pinfunction "C_C") (pintype "passive"))
    )
    (net (code "216") (name "Net-(PC4-PadA)") (class "Default")
      (node (ref "PC4") (pin "A") (pinfunction "A_A") (pintype "passive"))
      (node (ref "R11") (pin "2") (pinfunction "2_2") (pintype "passive"))
    )
    (net (code "217") (name "Net-(PC4-PadB)") (class "Default")
      (node (ref "PC4") (pin "B") (pinfunction "B_B") (pintype "passive"))
      (node (ref "T11") (pin "C") (pinfunction "C_C") (pintype "passive"))
    )
    (net (code "218") (name "Net-(PC5-PadA)") (class "Default")
      (node (ref "PC5") (pin "A") (pinfunction "A_A") (pintype "passive"))
      (node (ref "R12") (pin "2") (pinfunction "2_2") (pintype "passive"))
    )
    (net (code "219") (name "Net-(PC5-PadB)") (class "Default")
      (node (ref "PC5") (pin "B") (pinfunction "B_B") (pintype "passive"))
      (node (ref "T12") (pin "C") (pinfunction "C_C") (pintype "passive"))
    )
    (net (code "220") (name "Net-(PC6-PadA)") (class "Default")
      (node (ref "PC6") (pin "A") (pinfunction "A_A") (pintype "passive"))
      (node (ref "R13") (pin "2") (pinfunction "2_2") (pintype "passive"))
    )
    (net (code "221") (name "Net-(PC6-PadB)") (class "Default")
      (node (ref "PC6") (pin "B") (pinfunction "B_B") (pintype "passive"))
      (node (ref "T13") (pin "C") (pinfunction "C_C") (pintype "passive"))
    )
    (net (code "222") (name "Net-(PC7-PadA)") (class "Default")
      (node (ref "PC7") (pin "A") (pinfunction "A_A") (pintype "passive"))
      (node (ref "R14") (pin "2") (pinfunction "2_2") (pintype "passive"))
    )
    (net (code "223") (name "Net-(PC7-PadB)") (class "Default")
      (node (ref "PC7") (pin "B") (pinfunction "B_B") (pintype "passive"))
      (node (ref "T14") (pin "C") (pinfunction "C_C") (pintype "passive"))
    )
    (net (code "224") (name "Net-(PC8-PadA)") (class "Default")
      (node (ref "PC8") (pin "A") (pinfunction "A_A") (pintype "passive"))
      (node (ref "R15") (pin "2") (pinfunction "2_2") (pintype "passive"))
    )
    (net (code "225") (name "Net-(PC8-PadB)") (class "Default")
      (node (ref "PC8") (pin "B") (pinfunction "B_B") (pintype "passive"))
      (node (ref "T15") (pin "C") (pinfunction "C_C") (pintype "passive"))
    )
    (net (code "226") (name "Net-(PC9-PadA)") (class "Default")
      (node (ref "PC9") (pin "A") (pinfunction "A_A") (pintype "passive"))
      (node (ref "R16") (pin "2") (pinfunction "2_2") (pintype "passive"))
    )
    (net (code "227") (name "Net-(PC9-PadB)") (class "Default")
      (node (ref "PC9") (pin "B") (pinfunction "B_B") (pintype "passive"))
      (node (ref "T16") (pin "C") (pinfunction "C_C") (pintype "passive"))
    )
    (net (code "228") (name "Net-(PC10-PadA)") (class "Default")
      (node (ref "PC10") (pin "A") (pinfunction "A_A") (pintype "passive"))
      (node (ref "R17") (pin "2") (pinfunction "2_2") (pintype "passive"))
    )
    (net (code "229") (name "Net-(PC10-PadB)") (class "Default")
      (node (ref "PC10") (pin "B") (pinfunction "B_B") (pintype "passive"))
      (node (ref "T17") (pin "C") (pinfunction "C_C") (pintype "passive"))
    )
    (net (code "230") (name "Net-(PC11-PadA)") (class "Default")
      (node (ref "PC11") (pin "A") (pinfunction "A_A") (pintype "passive"))
      (node (ref "R18") (pin "2") (pinfunction "2_2") (pintype "passive"))
    )
    (net (code "231") (name "Net-(PC11-PadB)") (class "Default")
      (node (ref "PC11") (pin "B") (pinfunction "B_B") (pintype "passive"))
      (node (ref "T18") (pin "C") (pinfunction "C_C") (pintype "passive"))
    )
    (net (code "232") (name "Net-(R67-Pad2)") (class "Default")
      (node (ref "R67") (pin "2") (pinfunction "2_2") (pintype "passive"))
      (node (ref "SC0") (pin "A") (pinfunction "A_A") (pintype "passive"))
    )
    (net (code "233") (name "Net-(R68-Pad2)") (class "Default")
      (node (ref "R68") (pin "2") (pinfunction "2_2") (pintype "passive"))
      (node (ref "SC1") (pin "A") (pinfunction "A_A") (pintype "passive"))
    )
    (net (code "234") (name "Net-(R69-Pad2)") (class "Default")
      (node (ref "R69") (pin "2") (pinfunction "2_2") (pintype "passive"))
      (node (ref "SC2") (pin "A") (pinfunction "A_A") (pintype "passive"))
    )
    (net (code "235") (name "Net-(R70-Pad2)") (class "Default")
      (node (ref "R70") (pin "2") (pinfunction "2_2") (pintype "passive"))
      (node (ref "SC3") (pin "A") (pinfunction "A_A") (pintype "passive"))
    )
    (net (code "236") (name "Net-(R71-Pad2)") (class "Default")
      (node (ref "R71") (pin "2") (pinfunction "2_2") (pintype "passive"))
      (node (ref "SC4") (pin "A") (pinfunction "A_A") (pintype "passive"))
    )
    (net (code "237") (name "Net-(R75-Pad2)") (class "Default")
      (node (ref "R75") (pin "2") (pinfunction "2_2") (pintype "passive"))
      (node (ref "RUN") (pin "A") (pinfunction "A_A") (pintype "passive"))
    )
    (net (code "238") (name "Net-(R79-Pad2)") (class "Default")
      (node (ref "R79") (pin "2") (pinfunction "2_2") (pintype "passive"))
      (node (ref "WORDCOUNT") (pin "A") (pinfunction "A_A") (pintype "passive"))
    )
    (net (code "239") (name "Net-(R83-Pad2)") (class "Default")
      (node (ref "R83") (pin "2") (pinfunction "2_2") (pintype "passive"))
      (node (ref "TAD") (pin "A") (pinfunction "A_A") (pintype "passive"))
    )
    (net (code "240") (name "Net-(RUN-PadB)") (class "Default")
      (node (ref "RUN") (pin "B") (pinfunction "B_B") (pintype "passive"))
      (node (ref "T75") (pin "C") (pinfunction "C_C") (pintype "passive"))
    )
    (net (code "241") (name "Net-(SC0-PadB)") (class "Default")
      (node (ref "SC0") (pin "B") (pinfunction "B_B") (pintype "passive"))
      (node (ref "T67") (pin "C") (pinfunction "C_C") (pintype "passive"))
    )
    (net (code "242") (name "Net-(SC1-PadB)") (class "Default")
      (node (ref "SC1") (pin "B") (pinfunction "B_B") (pintype "passive"))
      (node (ref "T68") (pin "C") (pinfunction "C_C") (pintype "passive"))
    )
    (net (code "243") (name "Net-(SC2-PadB)") (class "Default")
      (node (ref "SC2") (pin "B") (pinfunction "B_B") (pintype "passive"))
      (node (ref "T69") (pin "C") (pinfunction "C_C") (pintype "passive"))
    )
    (net (code "244") (name "Net-(SC3-PadB)") (class "Default")
      (node (ref "SC3") (pin "B") (pinfunction "B_B") (pintype "passive"))
      (node (ref "T70") (pin "C") (pinfunction "C_C") (pintype "passive"))
    )
    (net (code "245") (name "Net-(SC4-PadB)") (class "Default")
      (node (ref "SC4") (pin "B") (pinfunction "B_B") (pintype "passive"))
      (node (ref "T71") (pin "C") (pinfunction "C_C") (pintype "passive"))
    )
    (net (code "246") (name "Net-(T79-PadC)") (class "Default")
      (node (ref "T79") (pin "C") (pinfunction "C_C") (pintype "passive"))
      (node (ref "WORDCOUNT") (pin "B") (pinfunction "B_B") (pintype "passive"))
    )
    (net (code "247") (name "Net-(T83-PadC)") (class "Default")
      (node (ref "T83") (pin "C") (pinfunction "C_C") (pintype "passive"))
      (node (ref "TAD") (pin "B") (pinfunction "B_B") (pintype "passive"))
    )
    (net (code "248") (name "OPR") (class "Default")
      (node (ref "D40") (pin "16") (pinfunction "16_16") (pintype "passive"))
      (node (ref "F40BOT") (pin "11") (pinfunction "1_11") (pintype "passive"))
      (node (ref "T89") (pin "B") (pinfunction "B_B") (pintype "passive"))
    )
    (net (code "249") (name "PAUSE") (class "Default")
      (node (ref "D40") (pin "31") (pinfunction "31_31") (pintype "passive"))
      (node (ref "F40TOP") (pin "17") (pinfunction "1_17") (pintype "passive"))
      (node (ref "T74") (pin "B") (pinfunction "B_B") (pintype "passive"))
    )
    (net (code "250") (name "PC0") (class "Default")
      (node (ref "D40TOP") (pin "1") (pinfunction "1_1") (pintype "passive"))
      (node (ref "E40") (pin "1") (pinfunction "1_1") (pintype "passive"))
      (node (ref "T7") (pin "B") (pinfunction "B_B") (pintype "passive"))
    )
    (net (code "251") (name "PC1") (class "Default")
      (node (ref "D40BOT") (pin "5") (pinfunction "1_5") (pintype "passive"))
      (node (ref "E40") (pin "10") (pinfunction "10_10") (pintype "passive"))
      (node (ref "T8") (pin "B") (pinfunction "B_B") (pintype "passive"))
    )
    (net (code "252") (name "PC2") (class "Default")
      (node (ref "D40TOP") (pin "6") (pinfunction "1_6") (pintype "passive"))
      (node (ref "E40") (pin "11") (pinfunction "11_11") (pintype "passive"))
      (node (ref "T9") (pin "B") (pinfunction "B_B") (pintype "passive"))
    )
    (net (code "253") (name "PC3") (class "Default")
      (node (ref "D40BOT") (pin "14") (pinfunction "1_14") (pintype "passive"))
      (node (ref "E40") (pin "24") (pinfunction "24_24") (pintype "passive"))
      (node (ref "T10") (pin "B") (pinfunction "B_B") (pintype "passive"))
    )
    (net (code "254") (name "PC4") (class "Default")
      (node (ref "D40TOP") (pin "14") (pinfunction "1_14") (pintype "passive"))
      (node (ref "E40") (pin "25") (pinfunction "25_25") (pintype "passive"))
      (node (ref "T11") (pin "B") (pinfunction "B_B") (pintype "passive"))
    )
    (net (code "255") (name "PC5") (class "Default")
      (node (ref "D40BOT") (pin "19") (pinfunction "1_19") (pintype "passive"))
      (node (ref "E40") (pin "34") (pinfunction "34_34") (pintype "passive"))
      (node (ref "T12") (pin "B") (pinfunction "B_B") (pintype "passive"))
    )
    (net (code "256") (name "PC6") (class "Default")
      (node (ref "E40TOP") (pin "1") (pinfunction "1_1") (pintype "passive"))
      (node (ref "F40") (pin "1") (pinfunction "1_1") (pintype "passive"))
      (node (ref "T13") (pin "B") (pinfunction "B_B") (pintype "passive"))
    )
    (net (code "257") (name "PC7") (class "Default")
      (node (ref "E40BOT") (pin "5") (pinfunction "1_5") (pintype "passive"))
      (node (ref "F40") (pin "10") (pinfunction "10_10") (pintype "passive"))
      (node (ref "T14") (pin "B") (pinfunction "B_B") (pintype "passive"))
    )
    (net (code "258") (name "PC8") (class "Default")
      (node (ref "E40TOP") (pin "6") (pinfunction "1_6") (pintype "passive"))
      (node (ref "F40") (pin "11") (pinfunction "11_11") (pintype "passive"))
      (node (ref "T15") (pin "B") (pinfunction "B_B") (pintype "passive"))
    )
    (net (code "259") (name "PC9") (class "Default")
      (node (ref "E40BOT") (pin "14") (pinfunction "1_14") (pintype "passive"))
      (node (ref "F40") (pin "24") (pinfunction "24_24") (pintype "passive"))
      (node (ref "T16") (pin "B") (pinfunction "B_B") (pintype "passive"))
    )
    (net (code "260") (name "PC10") (class "Default")
      (node (ref "E40TOP") (pin "14") (pinfunction "1_14") (pintype "passive"))
      (node (ref "F40") (pin "25") (pinfunction "25_25") (pintype "passive"))
      (node (ref "T17") (pin "B") (pinfunction "B_B") (pintype "passive"))
    )
    (net (code "261") (name "PC11") (class "Default")
      (node (ref "E40BOT") (pin "19") (pinfunction "1_19") (pintype "passive"))
      (node (ref "F40") (pin "34") (pinfunction "34_34") (pintype "passive"))
      (node (ref "T18") (pin "B") (pinfunction "B_B") (pintype "passive"))
    )
    (net (code "262") (name "RUN") (class "Default")
      (node (ref "D40") (pin "33") (pinfunction "33_33") (pintype "passive"))
      (node (ref "F40TOP") (pin "18") (pinfunction "1_18") (pintype "passive"))
      (node (ref "T75") (pin "B") (pinfunction "B_B") (pintype "passive"))
    )
    (net (code "263") (name "S$1") (class "Default")
      (node (ref "D40") (pin "23") (pinfunction "23_23") (pintype "passive"))
      (node (ref "F40TOP") (pin "13") (pinfunction "1_13") (pintype "passive"))
    )
    (net (code "264") (name "SC0") (class "Default")
      (node (ref "C40") (pin "9") (pinfunction "9_9") (pintype "passive"))
      (node (ref "C40TOP") (pin "5") (pinfunction "1_5") (pintype "passive"))
      (node (ref "T67") (pin "B") (pinfunction "B_B") (pintype "passive"))
    )
    (net (code "265") (name "SC1") (class "Default")
      (node (ref "C40") (pin "2") (pinfunction "2_2") (pintype "passive"))
      (node (ref "C40BOT") (pin "1") (pinfunction "1_1") (pintype "passive"))
      (node (ref "T68") (pin "B") (pinfunction "B_B") (pintype "passive"))
    )
    (net (code "266") (name "SC2") (class "Default")
      (node (ref "C40") (pin "23") (pinfunction "23_23") (pintype "passive"))
      (node (ref "C40TOP") (pin "13") (pinfunction "1_13") (pintype "passive"))
      (node (ref "T69") (pin "B") (pinfunction "B_B") (pintype "passive"))
    )
    (net (code "267") (name "SC3") (class "Default")
      (node (ref "C40") (pin "12") (pinfunction "12_12") (pintype "passive"))
      (node (ref "C40BOT") (pin "6") (pinfunction "1_6") (pintype "passive"))
      (node (ref "T70") (pin "B") (pinfunction "B_B") (pintype "passive"))
    )
    (net (code "268") (name "SC4") (class "Default")
      (node (ref "C40") (pin "33") (pinfunction "33_33") (pintype "passive"))
      (node (ref "C40TOP") (pin "18") (pinfunction "1_18") (pintype "passive"))
      (node (ref "T71") (pin "B") (pinfunction "B_B") (pintype "passive"))
    )
    (net (code "269") (name "TAD") (class "Default")
      (node (ref "D40") (pin "4") (pinfunction "4_4") (pintype "passive"))
      (node (ref "F40BOT") (pin "2") (pinfunction "1_2") (pintype "passive"))
      (node (ref "T83") (pin "B") (pinfunction "B_B") (pintype "passive"))
    )
    (net (code "270") (name "WC") (class "Default")
      (node (ref "D40") (pin "30") (pinfunction "30_30") (pintype "passive"))
      (node (ref "F40BOT") (pin "17") (pinfunction "1_17") (pintype "passive"))
      (node (ref "T79") (pin "B") (pinfunction "B_B") (pintype "passive"))
    )
    (net (code "271") (name "unconnected-(C40-Pad3)") (class "Default")
      (node (ref "C40") (pin "3") (pinfunction "3_3") (pintype "passive"))
    )
    (net (code "272") (name "unconnected-(C40-Pad4)") (class "Default")
      (node (ref "C40") (pin "4") (pinfunction "4_4") (pintype "passive"))
    )
    (net (code "273") (name "unconnected-(C40-Pad5)") (class "Default")
      (node (ref "C40") (pin "5") (pinfunction "5_5") (pintype "passive"))
    )
    (net (code "274") (name "unconnected-(C40-Pad6)") (class "Default")
      (node (ref "C40") (pin "6") (pinfunction "6_6") (pintype "passive"))
    )
    (net (code "275") (name "unconnected-(C40-Pad7)") (class "Default")
      (node (ref "C40") (pin "7") (pinfunction "7_7") (pintype "passive"))
    )
    (net (code "276") (name "unconnected-(C40-Pad8)") (class "Default")
      (node (ref "C40") (pin "8") (pinfunction "8_8") (pintype "passive"))
    )
    (net (code "277") (name "unconnected-(C40-Pad13)") (class "Default")
      (node (ref "C40") (pin "13") (pinfunction "13_13") (pintype "passive"))
    )
    (net (code "278") (name "unconnected-(C40-Pad14)") (class "Default")
      (node (ref "C40") (pin "14") (pinfunction "14_14") (pintype "passive"))
    )
    (net (code "279") (name "unconnected-(C40-Pad15)") (class "Default")
      (node (ref "C40") (pin "15") (pinfunction "15_15") (pintype "passive"))
    )
    (net (code "280") (name "unconnected-(C40-Pad16)") (class "Default")
      (node (ref "C40") (pin "16") (pinfunction "16_16") (pintype "passive"))
    )
    (net (code "281") (name "unconnected-(C40-Pad17)") (class "Default")
      (node (ref "C40") (pin "17") (pinfunction "17_17") (pintype "passive"))
    )
    (net (code "282") (name "unconnected-(C40-Pad18)") (class "Default")
      (node (ref "C40") (pin "18") (pinfunction "18_18") (pintype "passive"))
    )
    (net (code "283") (name "unconnected-(C40-Pad19)") (class "Default")
      (node (ref "C40") (pin "19") (pinfunction "19_19") (pintype "passive"))
    )
    (net (code "284") (name "unconnected-(C40-Pad20)") (class "Default")
      (node (ref "C40") (pin "20") (pinfunction "20_20") (pintype "passive"))
    )
    (net (code "285") (name "unconnected-(C40-Pad21)") (class "Default")
      (node (ref "C40") (pin "21") (pinfunction "21_21") (pintype "passive"))
    )
    (net (code "286") (name "unconnected-(C40-Pad22)") (class "Default")
      (node (ref "C40") (pin "22") (pinfunction "22_22") (pintype "passive"))
    )
    (net (code "287") (name "unconnected-(C40-Pad26)") (class "Default")
      (node (ref "C40") (pin "26") (pinfunction "26_26") (pintype "passive"))
    )
    (net (code "288") (name "unconnected-(C40-Pad27)") (class "Default")
      (node (ref "C40") (pin "27") (pinfunction "27_27") (pintype "passive"))
    )
    (net (code "289") (name "unconnected-(C40-Pad29)") (class "Default")
      (node (ref "C40") (pin "29") (pinfunction "29_29") (pintype "passive"))
    )
    (net (code "290") (name "unconnected-(C40-Pad30)") (class "Default")
      (node (ref "C40") (pin "30") (pinfunction "30_30") (pintype "passive"))
    )
    (net (code "291") (name "unconnected-(C40-Pad31)") (class "Default")
      (node (ref "C40") (pin "31") (pinfunction "31_31") (pintype "passive"))
    )
    (net (code "292") (name "unconnected-(C40-Pad32)") (class "Default")
      (node (ref "C40") (pin "32") (pinfunction "32_32") (pintype "passive"))
    )
    (net (code "293") (name "unconnected-(D40-Pad1)") (class "Default")
      (node (ref "D40") (pin "1") (pinfunction "1_1") (pintype "passive"))
    )
    (net (code "294") (name "unconnected-(D40-Pad3)") (class "Default")
      (node (ref "D40") (pin "3") (pinfunction "3_3") (pintype "passive"))
    )
    (net (code "295") (name "unconnected-(D40-Pad5)") (class "Default")
      (node (ref "D40") (pin "5") (pinfunction "5_5") (pintype "passive"))
    )
    (net (code "296") (name "unconnected-(D40-Pad7)") (class "Default")
      (node (ref "D40") (pin "7") (pinfunction "7_7") (pintype "passive"))
    )
    (net (code "297") (name "unconnected-(D40-Pad9)") (class "Default")
      (node (ref "D40") (pin "9") (pinfunction "9_9") (pintype "passive"))
    )
    (net (code "298") (name "unconnected-(D40-Pad11)") (class "Default")
      (node (ref "D40") (pin "11") (pinfunction "11_11") (pintype "passive"))
    )
    (net (code "299") (name "unconnected-(D40-Pad13)") (class "Default")
      (node (ref "D40") (pin "13") (pinfunction "13_13") (pintype "passive"))
    )
    (net (code "300") (name "unconnected-(D40-Pad15)") (class "Default")
      (node (ref "D40") (pin "15") (pinfunction "15_15") (pintype "passive"))
    )
    (net (code "301") (name "unconnected-(D40-Pad17)") (class "Default")
      (node (ref "D40") (pin "17") (pinfunction "17_17") (pintype "passive"))
    )
    (net (code "302") (name "unconnected-(D40-Pad18)") (class "Default")
      (node (ref "D40") (pin "18") (pinfunction "18_18") (pintype "passive"))
    )
    (net (code "303") (name "unconnected-(D40-Pad19)") (class "Default")
      (node (ref "D40") (pin "19") (pinfunction "19_19") (pintype "passive"))
    )
    (net (code "304") (name "unconnected-(D40-Pad20)") (class "Default")
      (node (ref "D40") (pin "20") (pinfunction "20_20") (pintype "passive"))
    )
    (net (code "305") (name "unconnected-(D40-Pad21)") (class "Default")
      (node (ref "D40") (pin "21") (pinfunction "21_21") (pintype "passive"))
    )
    (net (code "306") (name "unconnected-(D40-Pad25)") (class "Default")
      (node (ref "D40") (pin "25") (pinfunction "25_25") (pintype "passive"))
    )
    (net (code "307") (name "unconnected-(D40-Pad27)") (class "Default")
      (node (ref "D40") (pin "27") (pinfunction "27_27") (pintype "passive"))
    )
    (net (code "308") (name "unconnected-(D40-Pad29)") (class "Default")
      (node (ref "D40") (pin "29") (pinfunction "29_29") (pintype "passive"))
    )
    (net (code "309") (name "unconnected-(E40-Pad17)") (class "Default")
      (node (ref "E40") (pin "17") (pinfunction "17_17") (pintype "passive"))
    )
    (net (code "310") (name "unconnected-(E40-Pad18)") (class "Default")
      (node (ref "E40") (pin "18") (pinfunction "18_18") (pintype "passive"))
    )
    (net (code "311") (name "unconnected-(E40-Pad19)") (class "Default")
      (node (ref "E40") (pin "19") (pinfunction "19_19") (pintype "passive"))
    )
    (net (code "312") (name "unconnected-(E40-Pad20)") (class "Default")
      (node (ref "E40") (pin "20") (pinfunction "20_20") (pintype "passive"))
    )
    (net (code "313") (name "unconnected-(F40-Pad17)") (class "Default")
      (node (ref "F40") (pin "17") (pinfunction "17_17") (pintype "passive"))
    )
    (net (code "314") (name "unconnected-(F40-Pad18)") (class "Default")
      (node (ref "F40") (pin "18") (pinfunction "18_18") (pintype "passive"))
    )
    (net (code "315") (name "unconnected-(F40-Pad19)") (class "Default")
      (node (ref "F40") (pin "19") (pinfunction "19_19") (pintype "passive"))
    )
    (net (code "316") (name "unconnected-(F40-Pad20)") (class "Default")
      (node (ref "F40") (pin "20") (pinfunction "20_20") (pintype "passive"))
    )
    (net (code "317") (name "unconnected-(OPEN1-Pad1)") (class "Default")
      (node (ref "OPEN1") (pin "1") (pinfunction "1_1") (pintype "passive"))
    )
    (net (code "318") (name "unconnected-(OPEN2-Pad1)") (class "Default")
      (node (ref "OPEN2") (pin "1") (pinfunction "1_1") (pintype "passive"))
    )
  )
)
